# bontor_mbed_lowpan_rev_d.net
KiCad netlist of a schematic drawn in EAGLE
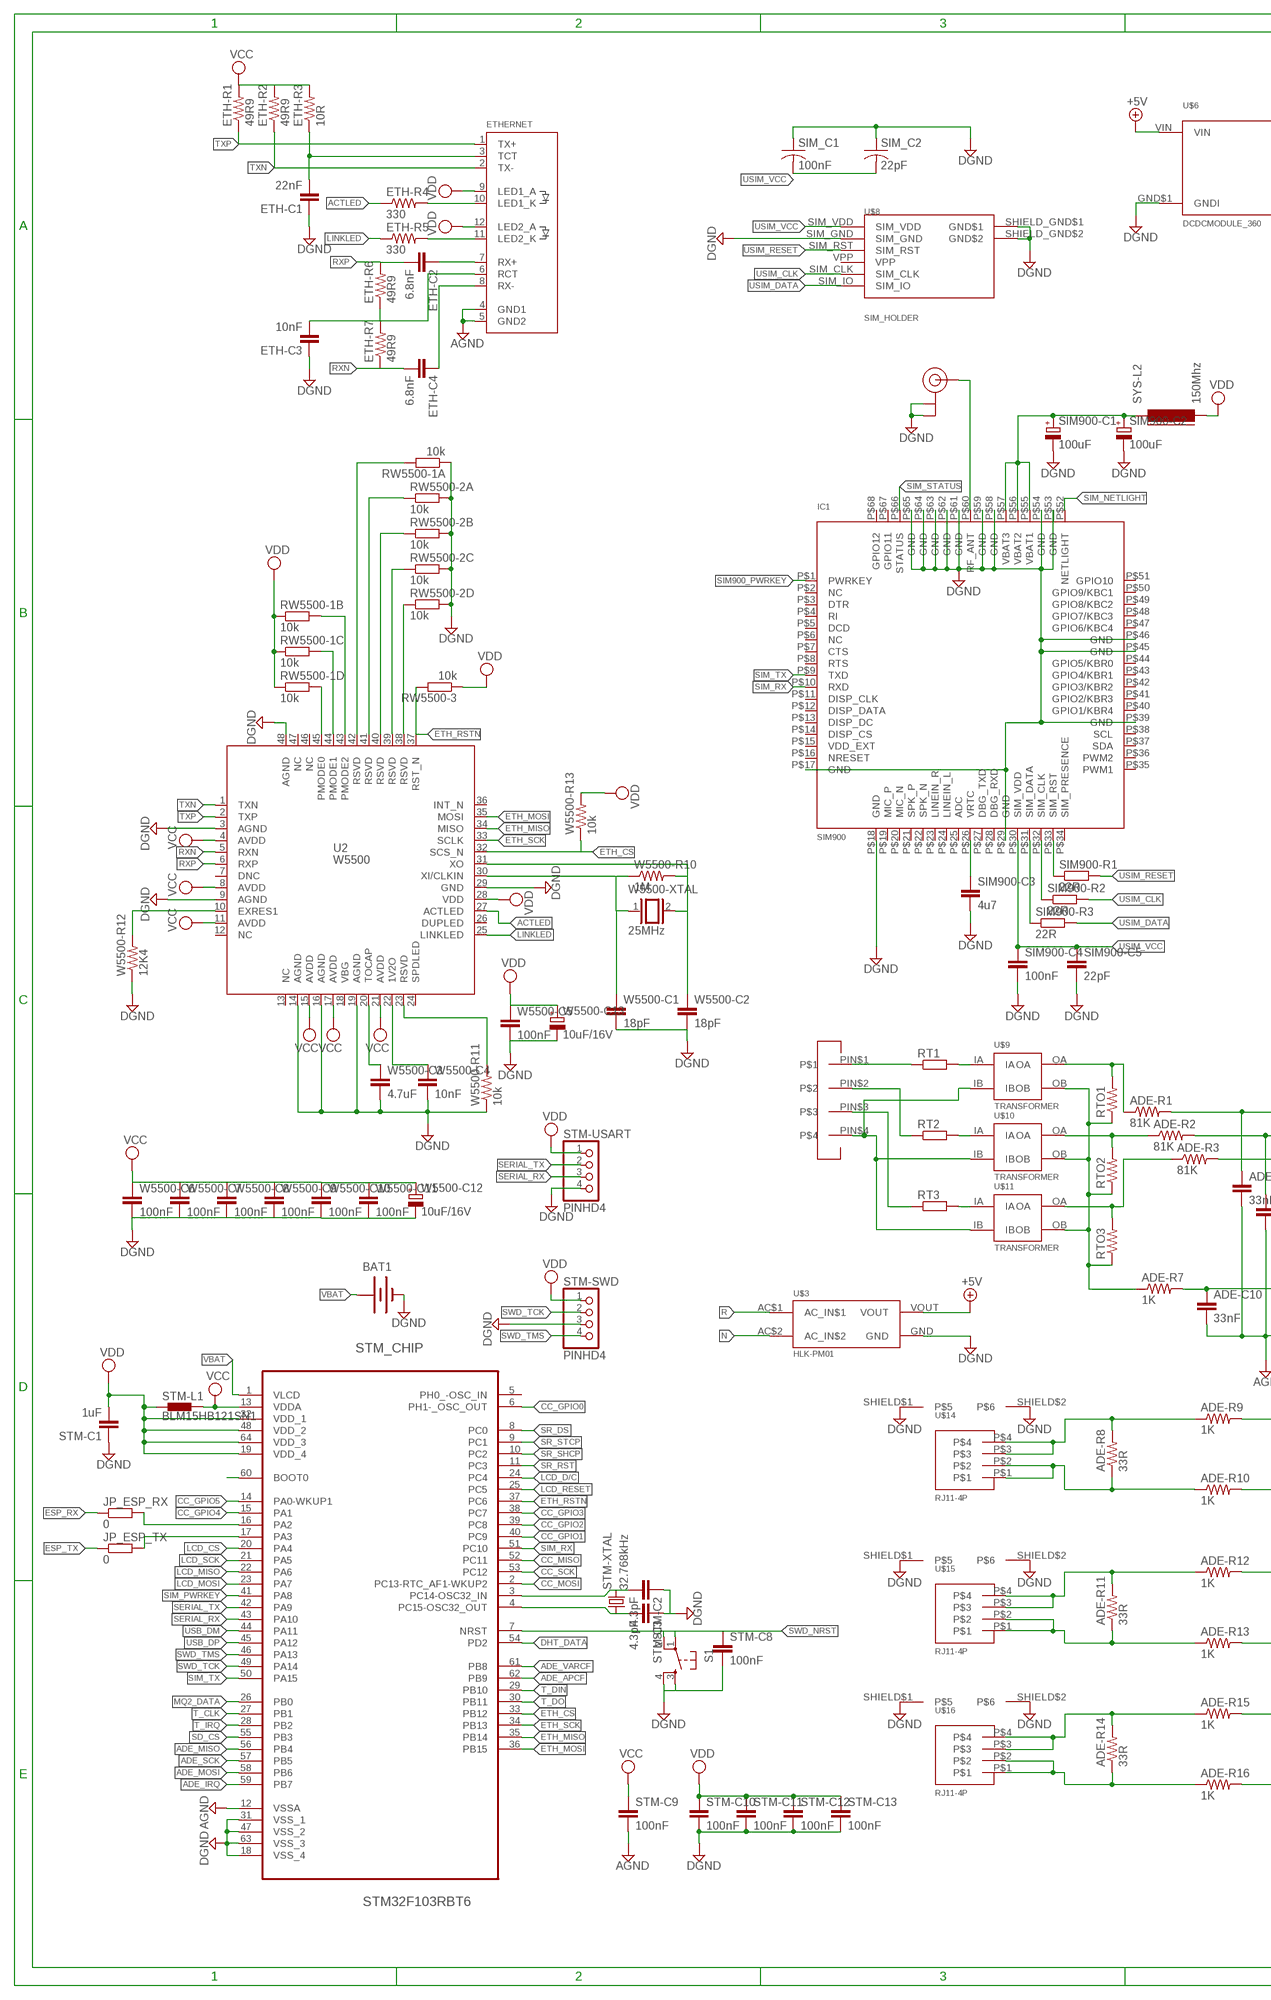
[diagram p0: schematic, sheet 1, part 1 of 2]
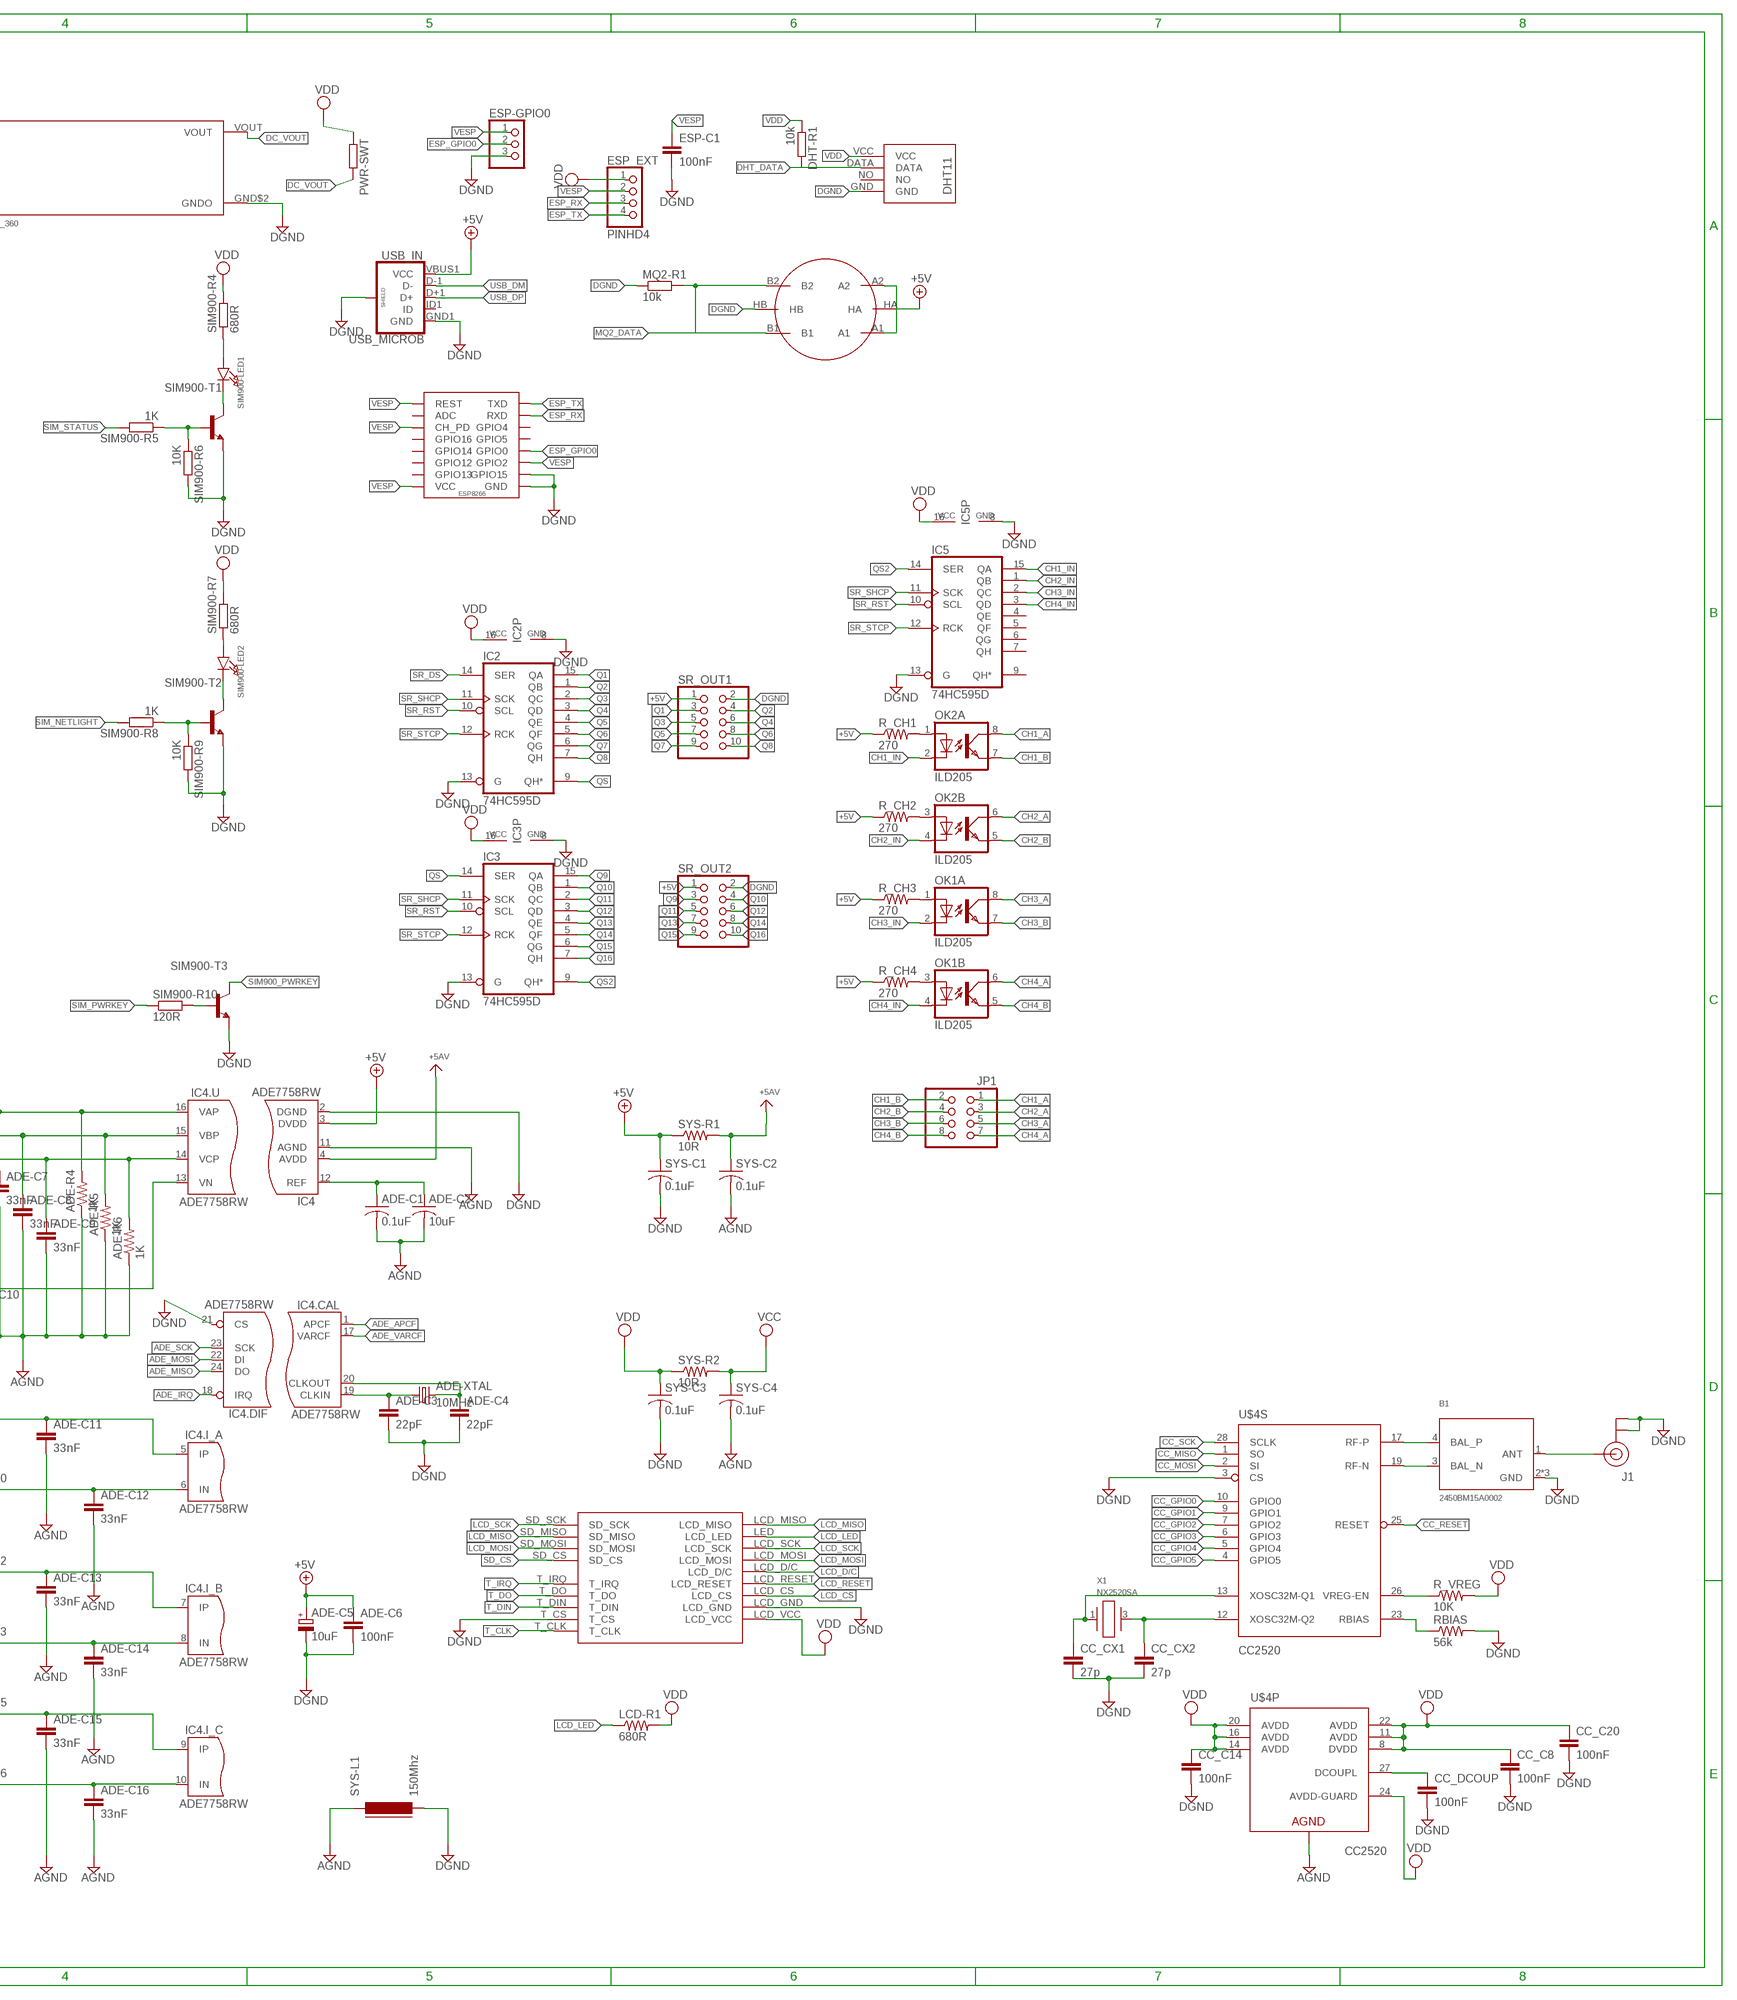
[diagram p1: schematic, sheet 1, part 2 of 2]

(export (version "E")
  (design (tool "Eeschema 10.0.6"))
  (components
    (comp (ref "ADE-C1")
      (value "0.1uF")
      (footprint "eagle-import:C0603@1")
      (libsource (lib "eagle-import") (part "C-USC0603"))
    )
    (comp (ref "ADE-C2")
      (value "10uF")
      (footprint "eagle-import:C0805K")
      (libsource (lib "eagle-import") (part "C-USC0805K"))
    )
    (comp (ref "ADE-C3")
      (value "22pF")
      (footprint "eagle-import:C0603")
      (libsource (lib "eagle-import") (part "C-EUC0603"))
    )
    (comp (ref "ADE-C4")
      (value "22pF")
      (footprint "eagle-import:C0603")
      (libsource (lib "eagle-import") (part "C-EUC0603"))
    )
    (comp (ref "ADE-C5")
      (value "10uF")
      (footprint "eagle-import:153CLV-0605")
      (libsource (lib "eagle-import") (part "CPOL-EU153CLV-0605"))
    )
    (comp (ref "ADE-C6")
      (value "100nF")
      (footprint "eagle-import:C0603")
      (libsource (lib "eagle-import") (part "C-EUC0603"))
    )
    (comp (ref "ADE-C7")
      (value "33nF")
      (footprint "eagle-import:0603-CAP")
      (libsource (lib "eagle-import") (part "CAP0603-CAP"))
    )
    (comp (ref "ADE-C8")
      (value "33nF")
      (footprint "eagle-import:0603-CAP")
      (libsource (lib "eagle-import") (part "CAP0603-CAP"))
    )
    (comp (ref "ADE-C9")
      (value "33nF")
      (footprint "eagle-import:0603-CAP")
      (libsource (lib "eagle-import") (part "CAP0603-CAP"))
    )
    (comp (ref "ADE-C10")
      (value "33nF")
      (footprint "eagle-import:0603-CAP")
      (libsource (lib "eagle-import") (part "CAP0603-CAP"))
    )
    (comp (ref "ADE-C11")
      (value "33nF")
      (footprint "eagle-import:0402-CAP")
      (libsource (lib "eagle-import") (part "CAP0402-CAP"))
    )
    (comp (ref "ADE-C12")
      (value "33nF")
      (footprint "eagle-import:0402-CAP")
      (libsource (lib "eagle-import") (part "CAP0402-CAP"))
    )
    (comp (ref "ADE-C13")
      (value "33nF")
      (footprint "eagle-import:0402-CAP")
      (libsource (lib "eagle-import") (part "CAP0402-CAP"))
    )
    (comp (ref "ADE-C14")
      (value "33nF")
      (footprint "eagle-import:0402-CAP")
      (libsource (lib "eagle-import") (part "CAP0402-CAP"))
    )
    (comp (ref "ADE-C15")
      (value "33nF")
      (footprint "eagle-import:0402-CAP")
      (libsource (lib "eagle-import") (part "CAP0402-CAP"))
    )
    (comp (ref "ADE-C16")
      (value "33nF")
      (footprint "eagle-import:0402-CAP")
      (libsource (lib "eagle-import") (part "CAP0402-CAP"))
    )
    (comp (ref "ADE-R1")
      (value "81K")
      (footprint "eagle-import:0603-RES")
      (libsource (lib "eagle-import") (part "RESISTOR0603-RES"))
    )
    (comp (ref "ADE-R2")
      (value "81K")
      (footprint "eagle-import:0603-RES")
      (libsource (lib "eagle-import") (part "RESISTOR0603-RES"))
    )
    (comp (ref "ADE-R3")
      (value "81K")
      (footprint "eagle-import:0603-RES")
      (libsource (lib "eagle-import") (part "RESISTOR0603-RES"))
    )
    (comp (ref "ADE-R4")
      (value "1K")
      (footprint "eagle-import:0603-RES")
      (libsource (lib "eagle-import") (part "RESISTOR0603-RES"))
    )
    (comp (ref "ADE-R5")
      (value "1K")
      (footprint "eagle-import:0603-RES")
      (libsource (lib "eagle-import") (part "RESISTOR0603-RES"))
    )
    (comp (ref "ADE-R6")
      (value "1K")
      (footprint "eagle-import:0603-RES")
      (libsource (lib "eagle-import") (part "RESISTOR0603-RES"))
    )
    (comp (ref "ADE-R7")
      (value "1K")
      (footprint "eagle-import:0603-RES")
      (libsource (lib "eagle-import") (part "RESISTOR0603-RES"))
    )
    (comp (ref "ADE-R8")
      (value "33R")
      (footprint "eagle-import:0402-RES")
      (libsource (lib "eagle-import") (part "RESISTOR0402-RES"))
    )
    (comp (ref "ADE-R9")
      (value "1K")
      (footprint "eagle-import:0402-RES")
      (libsource (lib "eagle-import") (part "RESISTOR0402-RES"))
    )
    (comp (ref "ADE-R10")
      (value "1K")
      (footprint "eagle-import:0402-RES")
      (libsource (lib "eagle-import") (part "RESISTOR0402-RES"))
    )
    (comp (ref "ADE-R11")
      (value "33R")
      (footprint "eagle-import:0402-RES")
      (libsource (lib "eagle-import") (part "RESISTOR0402-RES"))
    )
    (comp (ref "ADE-R12")
      (value "1K")
      (footprint "eagle-import:0402-RES")
      (libsource (lib "eagle-import") (part "RESISTOR0402-RES"))
    )
    (comp (ref "ADE-R13")
      (value "1K")
      (footprint "eagle-import:0402-RES")
      (libsource (lib "eagle-import") (part "RESISTOR0402-RES"))
    )
    (comp (ref "ADE-R14")
      (value "33R")
      (footprint "eagle-import:0402-RES")
      (libsource (lib "eagle-import") (part "RESISTOR0402-RES"))
    )
    (comp (ref "ADE-R15")
      (value "1K")
      (footprint "eagle-import:0402-RES")
      (libsource (lib "eagle-import") (part "RESISTOR0402-RES"))
    )
    (comp (ref "ADE-R16")
      (value "1K")
      (footprint "eagle-import:0402-RES")
      (libsource (lib "eagle-import") (part "RESISTOR0402-RES"))
    )
    (comp (ref "ADE-XTAL")
      (value "10MHz")
      (footprint "eagle-import:HC49US")
      (libsource (lib "eagle-import") (part "CRYSTALHC49US"))
    )
    (comp (ref "B1")
      (value "2450BM15A0002")
      (footprint "eagle-import:2450BM")
      (libsource (lib "eagle-import") (part "2450BM15A0002"))
    )
    (comp (ref "BAT1")
      (value "BATTERY12MM")
      (footprint "eagle-import:BATTCON_12MM")
      (libsource (lib "eagle-import") (part "BATTERY12MM"))
    )
    (comp (ref "CC_C8")
      (value "100nF")
      (footprint "eagle-import:C0402")
      (libsource (lib "eagle-import") (part "C-EUC0402"))
    )
    (comp (ref "CC_C14")
      (value "100nF")
      (footprint "eagle-import:C0402")
      (libsource (lib "eagle-import") (part "C-EUC0402"))
    )
    (comp (ref "CC_C20")
      (value "100nF")
      (footprint "eagle-import:C0402")
      (libsource (lib "eagle-import") (part "C-EUC0402"))
    )
    (comp (ref "CC_CX1")
      (value "27p")
      (footprint "eagle-import:C0201")
      (libsource (lib "eagle-import") (part "C-EUC0201"))
    )
    (comp (ref "CC_CX2")
      (value "27p")
      (footprint "eagle-import:C0201")
      (libsource (lib "eagle-import") (part "C-EUC0201"))
    )
    (comp (ref "CC_DCOUP")
      (value "100nF")
      (footprint "eagle-import:C0402")
      (libsource (lib "eagle-import") (part "C-EUC0402"))
    )
    (comp (ref "DHT-R1")
      (value "10k")
      (footprint "eagle-import:R0603")
      (libsource (lib "eagle-import") (part "resistor_R-EU_R0603"))
    )
    (comp (ref "ESP-C1")
      (value "100nF")
      (footprint "eagle-import:C0603")
      (libsource (lib "eagle-import") (part "C-EUC0603"))
    )
    (comp (ref "ESP-GPIO0")
      (value "PINHD-1X3")
      (footprint "eagle-import:1X03")
      (libsource (lib "eagle-import") (part "PINHD-1X3"))
    )
    (comp (ref "ESP_EXT")
      (value "PINHD4")
      (footprint "eagle-import:PINHD4")
      (libsource (lib "eagle-import") (part "PINHD4"))
    )
    (comp (ref "ETH-C1")
      (value "22nF")
      (footprint "eagle-import:C0603")
      (libsource (lib "eagle-import") (part "C-EUC0603"))
    )
    (comp (ref "ETH-C2")
      (value "6.8nF")
      (footprint "eagle-import:C0603")
      (libsource (lib "eagle-import") (part "C-EUC0603"))
    )
    (comp (ref "ETH-C3")
      (value "10nF")
      (footprint "eagle-import:C0603")
      (libsource (lib "eagle-import") (part "C-EUC0603"))
    )
    (comp (ref "ETH-C4")
      (value "6.8nF")
      (footprint "eagle-import:C0603")
      (libsource (lib "eagle-import") (part "C-EUC0603"))
    )
    (comp (ref "ETH-R1")
      (value "49R9")
      (footprint "eagle-import:R0603")
      (libsource (lib "eagle-import") (part "resistor_R-US_R0603"))
    )
    (comp (ref "ETH-R2")
      (value "49R9")
      (footprint "eagle-import:R0603")
      (libsource (lib "eagle-import") (part "resistor_R-US_R0603"))
    )
    (comp (ref "ETH-R3")
      (value "10R")
      (footprint "eagle-import:R0603")
      (libsource (lib "eagle-import") (part "resistor_R-US_R0603"))
    )
    (comp (ref "ETH-R4")
      (value "330")
      (footprint "eagle-import:R0603")
      (libsource (lib "eagle-import") (part "resistor_R-US_R0603"))
    )
    (comp (ref "ETH-R5")
      (value "330")
      (footprint "eagle-import:R0603")
      (libsource (lib "eagle-import") (part "resistor_R-US_R0603"))
    )
    (comp (ref "ETH-R6")
      (value "49R9")
      (footprint "eagle-import:R0603")
      (libsource (lib "eagle-import") (part "resistor_R-US_R0603"))
    )
    (comp (ref "ETH-R7")
      (value "49R9")
      (footprint "eagle-import:R0603")
      (libsource (lib "eagle-import") (part "resistor_R-US_R0603"))
    )
    (comp (ref "ETHERNET")
      (value "RJ45J0026D21BNL")
      (footprint "eagle-import:RJ45_PULSEJACK")
      (libsource (lib "eagle-import") (part "RJ45J0026D21BNL"))
    )
    (comp (ref "IC1")
      (value "SIM900")
      (footprint "eagle-import:SIM900_SMT")
      (libsource (lib "eagle-import") (part "GSM_SIM900_LITERAL"))
    )
    (comp (ref "IC2")
      (value "74HC595D")
      (footprint "eagle-import:SO16")
      (libsource (lib "eagle-import") (part "74595DHC"))
    )
    (comp (ref "IC3")
      (value "74HC595D")
      (footprint "eagle-import:SO16")
      (libsource (lib "eagle-import") (part "74595DHC"))
    )
    (comp (ref "IC4")
      (value "ADE7758RW")
      (footprint "eagle-import:SOIC24")
      (libsource (lib "eagle-import") (part "ADE7758RW"))
    )
    (comp (ref "IC5")
      (value "74HC595D")
      (footprint "eagle-import:SO16")
      (libsource (lib "eagle-import") (part "74595DHC"))
    )
    (comp (ref "J1")
      (value "U.FL")
      (footprint "eagle-import:U.FL")
      (libsource (lib "eagle-import") (part "SparkFun-Connectors_U.FL"))
    )
    (comp (ref "JP1")
      (value "PINHD-2X4")
      (footprint "eagle-import:2X04")
      (libsource (lib "eagle-import") (part "PINHD-2X4"))
    )
    (comp (ref "JP_ESP_RX")
      (value "0")
      (footprint "eagle-import:R0201")
      (libsource (lib "eagle-import") (part "R-EU_R0201"))
    )
    (comp (ref "JP_ESP_TX")
      (value "0")
      (footprint "eagle-import:R0201")
      (libsource (lib "eagle-import") (part "R-EU_R0201"))
    )
    (comp (ref "LCD-R1")
      (value "680R")
      (footprint "eagle-import:0603-RES")
      (libsource (lib "eagle-import") (part "RESISTOR0603-RES"))
    )
    (comp (ref "MQ2-R1")
      (value "10k")
      (footprint "eagle-import:R0603")
      (libsource (lib "eagle-import") (part "resistor_R-EU_R0603"))
    )
    (comp (ref "OK1")
      (value "ILD205")
      (footprint "eagle-import:SOIC08")
      (fields (field (name "MF") "VISHAY/TELEFUNKEN") (field (name "MPN") "ILD205T"))
      (libsource (lib "eagle-import") (part "ILD205"))
    )
    (comp (ref "OK2")
      (value "ILD205")
      (footprint "eagle-import:SOIC08")
      (fields (field (name "MF") "VISHAY/TELEFUNKEN") (field (name "MPN") "ILD205T"))
      (libsource (lib "eagle-import") (part "ILD205"))
    )
    (comp (ref "PWR-SWT")
      (value "R-EU_R0402")
      (footprint "eagle-import:R0402")
      (libsource (lib "eagle-import") (part "R-EU_R0402"))
    )
    (comp (ref "RBIAS")
      (value "56k")
      (footprint "eagle-import:0402-RES")
      (libsource (lib "eagle-import") (part "RESISTOR0402-RES"))
    )
    (comp (ref "RT1")
      (value "R-EU_0309/V")
      (footprint "eagle-import:0309V")
      (libsource (lib "eagle-import") (part "R-EU_0309/V"))
    )
    (comp (ref "RT2")
      (value "R-EU_0309/V")
      (footprint "eagle-import:0309V")
      (libsource (lib "eagle-import") (part "R-EU_0309/V"))
    )
    (comp (ref "RT3")
      (value "R-EU_0309/V")
      (footprint "eagle-import:0309V")
      (libsource (lib "eagle-import") (part "R-EU_0309/V"))
    )
    (comp (ref "RTO1")
      (value "R-US_0309_12")
      (footprint "eagle-import:0309_12")
      (libsource (lib "eagle-import") (part "R-US_0309_12"))
    )
    (comp (ref "RTO2")
      (value "R-US_0309_12")
      (footprint "eagle-import:0309_12")
      (libsource (lib "eagle-import") (part "R-US_0309_12"))
    )
    (comp (ref "RTO3")
      (value "R-US_0309_12")
      (footprint "eagle-import:0309_12")
      (libsource (lib "eagle-import") (part "R-US_0309_12"))
    )
    (comp (ref "RW5500-1")
      (value "10k")
      (footprint "eagle-import:RN8P-4R-CRA06S")
      (libsource (lib "eagle-import") (part "RESISTOR_ARRAY_4"))
    )
    (comp (ref "RW5500-2")
      (value "10k")
      (footprint "eagle-import:RN8P-4R-CRA06S")
      (libsource (lib "eagle-import") (part "RESISTOR_ARRAY_4"))
    )
    (comp (ref "RW5500-3")
      (value "10k")
      (footprint "eagle-import:R0603")
      (libsource (lib "eagle-import") (part "R-EU_R0603"))
    )
    (comp (ref "R_CH1")
      (value "270")
      (footprint "eagle-import:0603-RES")
      (libsource (lib "eagle-import") (part "RESISTOR0603-RES"))
    )
    (comp (ref "R_CH2")
      (value "270")
      (footprint "eagle-import:0603-RES")
      (libsource (lib "eagle-import") (part "RESISTOR0603-RES"))
    )
    (comp (ref "R_CH3")
      (value "270")
      (footprint "eagle-import:0603-RES")
      (libsource (lib "eagle-import") (part "RESISTOR0603-RES"))
    )
    (comp (ref "R_CH4")
      (value "270")
      (footprint "eagle-import:0603-RES")
      (libsource (lib "eagle-import") (part "RESISTOR0603-RES"))
    )
    (comp (ref "R_VREG")
      (value "10K")
      (footprint "eagle-import:0402-RES")
      (libsource (lib "eagle-import") (part "RESISTOR0402-RES"))
    )
    (comp (ref "S1")
      (value "TAC_SWITCHSMD")
      (footprint "eagle-import:TACTILE-SWITCH-SMD")
      (libsource (lib "eagle-import") (part "TAC_SWITCHSMD"))
    )
    (comp (ref "SENSOR-MQ2")
      (value "METHANE_SENSOR")
      (footprint "eagle-import:MQ-3")
      (libsource (lib "eagle-import") (part "METHANE_SENSOR"))
    )
    (comp (ref "SIM900-C1")
      (value "100uF")
      (footprint "eagle-import:153CLV-0605")
      (libsource (lib "eagle-import") (part "CPOL-EU153CLV-0605"))
    )
    (comp (ref "SIM900-C2")
      (value "100uF")
      (footprint "eagle-import:153CLV-0605")
      (libsource (lib "eagle-import") (part "CPOL-EU153CLV-0605"))
    )
    (comp (ref "SIM900-C3")
      (value "4u7")
      (footprint "eagle-import:C0603")
      (libsource (lib "eagle-import") (part "C-EUC0603"))
    )
    (comp (ref "SIM900-C4")
      (value "100nF")
      (footprint "eagle-import:C0603")
      (libsource (lib "eagle-import") (part "C-EUC0603"))
    )
    (comp (ref "SIM900-C5")
      (value "22pF")
      (footprint "eagle-import:C0603")
      (libsource (lib "eagle-import") (part "C-EUC0603"))
    )
    (comp (ref "SIM900-LED1")
      (value "LED0805_NOOUTLINE")
      (footprint "eagle-import:CHIPLED_0805_NOOUTLINE")
      (libsource (lib "eagle-import") (part "LED0805_NOOUTLINE"))
    )
    (comp (ref "SIM900-LED2")
      (value "LED0805_NOOUTLINE")
      (footprint "eagle-import:CHIPLED_0805_NOOUTLINE")
      (libsource (lib "eagle-import") (part "LED0805_NOOUTLINE"))
    )
    (comp (ref "SIM900-R1")
      (value "22R")
      (footprint "eagle-import:R0603")
      (libsource (lib "eagle-import") (part "R-EU_R0603"))
    )
    (comp (ref "SIM900-R2")
      (value "22R")
      (footprint "eagle-import:R0603")
      (libsource (lib "eagle-import") (part "R-EU_R0603"))
    )
    (comp (ref "SIM900-R3")
      (value "22R")
      (footprint "eagle-import:R0603")
      (libsource (lib "eagle-import") (part "R-EU_R0603"))
    )
    (comp (ref "SIM900-R4")
      (value "680R")
      (footprint "eagle-import:R0402")
      (libsource (lib "eagle-import") (part "R-EU_R0402"))
    )
    (comp (ref "SIM900-R5")
      (value "1K")
      (footprint "eagle-import:R0603")
      (libsource (lib "eagle-import") (part "R-EU_R0603"))
    )
    (comp (ref "SIM900-R6")
      (value "10K")
      (footprint "eagle-import:R0603")
      (libsource (lib "eagle-import") (part "R-EU_R0603"))
    )
    (comp (ref "SIM900-R7")
      (value "680R")
      (footprint "eagle-import:R0603")
      (libsource (lib "eagle-import") (part "R-EU_R0603"))
    )
    (comp (ref "SIM900-R8")
      (value "1K")
      (footprint "eagle-import:R0603")
      (libsource (lib "eagle-import") (part "R-EU_R0603"))
    )
    (comp (ref "SIM900-R9")
      (value "10K")
      (footprint "eagle-import:R0603")
      (libsource (lib "eagle-import") (part "R-EU_R0603"))
    )
    (comp (ref "SIM900-R10")
      (value "120R")
      (footprint "eagle-import:R0603")
      (libsource (lib "eagle-import") (part "resistor_R-EU_R0603"))
    )
    (comp (ref "SIM900-T1")
      (value "MMBT2222ALT1-NPN-SOT23-BEC")
      (footprint "eagle-import:SOT23-BEC")
      (libsource (lib "eagle-import") (part "-NPN-SOT23-BECMMBT2222ALT1"))
    )
    (comp (ref "SIM900-T2")
      (value "MMBT2222ALT1-NPN-SOT23-BEC")
      (footprint "eagle-import:SOT23-BEC")
      (libsource (lib "eagle-import") (part "-NPN-SOT23-BECMMBT2222ALT1"))
    )
    (comp (ref "SIM900-T3")
      (value "MMBT2222ALT1-NPN-SOT23-BEC")
      (footprint "eagle-import:SOT23-BEC")
      (libsource (lib "eagle-import") (part "transistor-neu-to92_-NPN-SOT23-BECMMBT2222ALT1"))
    )
    (comp (ref "SIM_C1")
      (value "100nF")
      (footprint "eagle-import:C0603K")
      (libsource (lib "eagle-import") (part "C-USC0603K"))
    )
    (comp (ref "SIM_C2")
      (value "22pF")
      (footprint "eagle-import:C0603K")
      (libsource (lib "eagle-import") (part "C-USC0603K"))
    )
    (comp (ref "SR_OUT1")
      (value "PINHD-2X5")
      (footprint "eagle-import:2X05")
      (libsource (lib "eagle-import") (part "PINHD-2X5"))
    )
    (comp (ref "SR_OUT2")
      (value "PINHD-2X5")
      (footprint "eagle-import:2X05")
      (libsource (lib "eagle-import") (part "PINHD-2X5"))
    )
    (comp (ref "STM-C1")
      (value "1uF")
      (footprint "eagle-import:C0603")
      (libsource (lib "eagle-import") (part "C-EUC0603"))
    )
    (comp (ref "STM-C2")
      (value "4.3pF")
      (footprint "eagle-import:C0603")
      (libsource (lib "eagle-import") (part "C-EUC0603"))
    )
    (comp (ref "STM-C3")
      (value "4.3pF")
      (footprint "eagle-import:C0603")
      (libsource (lib "eagle-import") (part "C-EUC0603"))
    )
    (comp (ref "STM-C8")
      (value "100nF")
      (footprint "eagle-import:C0603")
      (libsource (lib "eagle-import") (part "C-EUC0603"))
    )
    (comp (ref "STM-C9")
      (value "100nF")
      (footprint "eagle-import:C0603")
      (libsource (lib "eagle-import") (part "C-EUC0603"))
    )
    (comp (ref "STM-C10")
      (value "100nF")
      (footprint "eagle-import:C0603")
      (libsource (lib "eagle-import") (part "C-EUC0603"))
    )
    (comp (ref "STM-C11")
      (value "100nF")
      (footprint "eagle-import:C0603")
      (libsource (lib "eagle-import") (part "C-EUC0603"))
    )
    (comp (ref "STM-C12")
      (value "100nF")
      (footprint "eagle-import:C0603")
      (libsource (lib "eagle-import") (part "C-EUC0603"))
    )
    (comp (ref "STM-C13")
      (value "100nF")
      (footprint "eagle-import:C0603")
      (libsource (lib "eagle-import") (part "C-EUC0603"))
    )
    (comp (ref "STM-L1")
      (value "BLM15HB121SN1")
      (footprint "eagle-import:0402")
      (libsource (lib "eagle-import") (part "BLM15HB121SN1"))
    )
    (comp (ref "STM-SWD")
      (value "PINHD4")
      (footprint "eagle-import:PINHD4")
      (libsource (lib "eagle-import") (part "PINHD4"))
    )
    (comp (ref "STM-USART")
      (value "PINHD4")
      (footprint "eagle-import:PINHD4")
      (libsource (lib "eagle-import") (part "PINHD4"))
    )
    (comp (ref "STM-XTAL")
      (value "32.768kHz")
      (footprint "eagle-import:TC26H")
      (libsource (lib "eagle-import") (part "CRYSTALTC26H"))
    )
    (comp (ref "STM_CHIP")
      (value "STM32F103RBT6")
      (footprint "eagle-import:QFP50P1200X1200X160-64N")
      (fields (field (name "MPN") "STM32L152RBT6"))
      (libsource (lib "eagle-import") (part "STM32L152RBT6"))
    )
    (comp (ref "SYS-C1")
      (value "0.1uF")
      (footprint "eagle-import:C0603@1")
      (libsource (lib "eagle-import") (part "C-USC0603"))
    )
    (comp (ref "SYS-C2")
      (value "0.1uF")
      (footprint "eagle-import:C0603@1")
      (libsource (lib "eagle-import") (part "C-USC0603"))
    )
    (comp (ref "SYS-C3")
      (value "0.1uF")
      (footprint "eagle-import:C0603@1")
      (libsource (lib "eagle-import") (part "C-USC0603"))
    )
    (comp (ref "SYS-C4")
      (value "0.1uF")
      (footprint "eagle-import:C0603@1")
      (libsource (lib "eagle-import") (part "C-USC0603"))
    )
    (comp (ref "SYS-L1")
      (value "150Mhz")
      (footprint "eagle-import:FB805")
      (libsource (lib "eagle-import") (part "FERRITE-0805"))
    )
    (comp (ref "SYS-L2")
      (value "150Mhz")
      (footprint "eagle-import:FB805")
      (libsource (lib "eagle-import") (part "FERRITE-0805"))
    )
    (comp (ref "SYS-R1")
      (value "10R")
      (footprint "eagle-import:0603-RES")
      (libsource (lib "eagle-import") (part "RESISTOR0603-RES"))
    )
    (comp (ref "SYS-R2")
      (value "10R")
      (footprint "eagle-import:0603-RES")
      (libsource (lib "eagle-import") (part "RESISTOR0603-RES"))
    )
    (comp (ref "U$3")
      (value "HLK-PM01")
      (footprint "eagle-import:HLK-PM01")
      (libsource (lib "eagle-import") (part "HLK-PM01"))
    )
    (comp (ref "U$4")
      (value "CC2520")
      (footprint "eagle-import:QFN50P500X500X100-29N")
      (libsource (lib "eagle-import") (part "CC2520"))
    )
    (comp (ref "U$5")
      (value "ESP8266WI12")
      (footprint "eagle-import:WI12")
      (libsource (lib "eagle-import") (part "ESP8266WI12"))
    )
    (comp (ref "U$6")
      (value "DCDCMODULE_360")
      (footprint "eagle-import:DCDCMODULE-360")
      (libsource (lib "eagle-import") (part "DCDCMODULE_360"))
    )
    (comp (ref "U$7")
      (value "U.FL")
      (footprint "eagle-import:U.FL")
      (libsource (lib "eagle-import") (part "U.FL"))
    )
    (comp (ref "U$8")
      (value "SIM_HOLDER")
      (footprint "eagle-import:SIMHOLDER-PUSHPUSH")
      (libsource (lib "eagle-import") (part "SIM_HOLDER"))
    )
    (comp (ref "U$9")
      (value "TRANSFORMER")
      (footprint "eagle-import:TV16")
      (libsource (lib "eagle-import") (part "TRANSFORMER"))
    )
    (comp (ref "U$10")
      (value "TRANSFORMER")
      (footprint "eagle-import:TV16")
      (libsource (lib "eagle-import") (part "TRANSFORMER"))
    )
    (comp (ref "U$11")
      (value "TRANSFORMER")
      (footprint "eagle-import:TV16")
      (libsource (lib "eagle-import") (part "TRANSFORMER"))
    )
    (comp (ref "U$12")
      (value "TERMINAL_BLOCK_TW")
      (footprint "eagle-import:TERMINAL-TWO-WAY")
      (libsource (lib "eagle-import") (part "TERMINAL_BLOCK_TW"))
    )
    (comp (ref "U$13")
      (value "LCD_2.4")
      (footprint "eagle-import:LCD_TOUCH_2-4")
      (libsource (lib "eagle-import") (part "LCD_2.4"))
    )
    (comp (ref "U$14")
      (value "RJ11-4P")
      (footprint "eagle-import:RJ11-4P")
      (libsource (lib "eagle-import") (part "RJ11-4P"))
    )
    (comp (ref "U$15")
      (value "RJ11-4P")
      (footprint "eagle-import:RJ11-4P")
      (libsource (lib "eagle-import") (part "RJ11-4P"))
    )
    (comp (ref "U$16")
      (value "RJ11-4P")
      (footprint "eagle-import:RJ11-4P")
      (libsource (lib "eagle-import") (part "RJ11-4P"))
    )
    (comp (ref "U$17")
      (value "DHT11")
      (footprint "eagle-import:DHT11")
      (libsource (lib "eagle-import") (part "DHT11"))
    )
    (comp (ref "U2")
      (value "W5500")
      (footprint "eagle-import:W5500")
      (libsource (lib "eagle-import") (part "W5500"))
    )
    (comp (ref "USB_IN")
      (value "USB_MICROB")
      (footprint "eagle-import:USB-B-MICRO-SMD_V03")
      (libsource (lib "eagle-import") (part "USB_MICROB_PLUGCONN-11752"))
    )
    (comp (ref "W5500-C1")
      (value "18pF")
      (footprint "eagle-import:C0603")
      (libsource (lib "eagle-import") (part "C-EUC0603"))
    )
    (comp (ref "W5500-C2")
      (value "18pF")
      (footprint "eagle-import:C0603")
      (libsource (lib "eagle-import") (part "C-EUC0603"))
    )
    (comp (ref "W5500-C3")
      (value "4.7uF")
      (footprint "eagle-import:C0603")
      (libsource (lib "eagle-import") (part "C-EUC0603"))
    )
    (comp (ref "W5500-C4")
      (value "10nF")
      (footprint "eagle-import:C0603")
      (libsource (lib "eagle-import") (part "C-EUC0603"))
    )
    (comp (ref "W5500-C5")
      (value "100nF")
      (footprint "eagle-import:C0603")
      (libsource (lib "eagle-import") (part "C-EUC0603"))
    )
    (comp (ref "W5500-C6")
      (value "100nF")
      (footprint "eagle-import:C0603")
      (libsource (lib "eagle-import") (part "C-EUC0603"))
    )
    (comp (ref "W5500-C7")
      (value "100nF")
      (footprint "eagle-import:C0603")
      (libsource (lib "eagle-import") (part "C-EUC0603"))
    )
    (comp (ref "W5500-C8")
      (value "100nF")
      (footprint "eagle-import:C0603")
      (libsource (lib "eagle-import") (part "C-EUC0603"))
    )
    (comp (ref "W5500-C9")
      (value "100nF")
      (footprint "eagle-import:C0603")
      (libsource (lib "eagle-import") (part "C-EUC0603"))
    )
    (comp (ref "W5500-C10")
      (value "100nF")
      (footprint "eagle-import:C0603")
      (libsource (lib "eagle-import") (part "C-EUC0603"))
    )
    (comp (ref "W5500-C11")
      (value "100nF")
      (footprint "eagle-import:C0603")
      (libsource (lib "eagle-import") (part "C-EUC0603"))
    )
    (comp (ref "W5500-C12")
      (value "10uF/16V")
      (footprint "eagle-import:153CLV-0605")
      (libsource (lib "eagle-import") (part "CPOL-EU153CLV-0605"))
    )
    (comp (ref "W5500-C13")
      (value "10uF/16V")
      (footprint "eagle-import:153CLV-0605")
      (libsource (lib "eagle-import") (part "CPOL-EU153CLV-0605"))
    )
    (comp (ref "W5500-R10")
      (value "1M")
      (footprint "eagle-import:R0603")
      (libsource (lib "eagle-import") (part "resistor_R-US_R0603"))
    )
    (comp (ref "W5500-R11")
      (value "10k")
      (footprint "eagle-import:R0603")
      (libsource (lib "eagle-import") (part "resistor_R-US_R0603"))
    )
    (comp (ref "W5500-R12")
      (value "12K4")
      (footprint "eagle-import:R0805")
      (libsource (lib "eagle-import") (part "resistor_R-US_R0805"))
    )
    (comp (ref "W5500-R13")
      (value "10k")
      (footprint "eagle-import:R0603")
      (libsource (lib "eagle-import") (part "resistor_R-US_R0603"))
    )
    (comp (ref "W5500-XTAL")
      (value "25MHz")
      (footprint "eagle-import:QS")
      (libsource (lib "eagle-import") (part "XTAL/S"))
    )
    (comp (ref "X1")
      (value "NX2520SA")
      (footprint "eagle-import:NX2520SA")
      (libsource (lib "eagle-import") (part "NX2520SA"))
    )
  )
  (nets
    (net (code "1") (name "+5AV") (class "Default")
      (node (ref "IC4") (pin "4") (pinfunction "AVDD_4") (pintype "power_in"))
      (node (ref "SYS-C2") (pin "1") (pinfunction "1_1") (pintype "passive"))
      (node (ref "SYS-R1") (pin "2") (pinfunction "2_2") (pintype "passive"))
    )
    (net (code "2") (name "+5V") (class "Default")
      (node (ref "ADE-C5") (pin "+") (pinfunction "+_+") (pintype "passive"))
      (node (ref "ADE-C6") (pin "1") (pinfunction "1_1") (pintype "passive"))
      (node (ref "IC4") (pin "3") (pinfunction "DVDD_3") (pintype "power_in"))
      (node (ref "R_CH1") (pin "1") (pinfunction "1_1") (pintype "passive"))
      (node (ref "R_CH2") (pin "1") (pinfunction "1_1") (pintype "passive"))
      (node (ref "R_CH3") (pin "1") (pinfunction "1_1") (pintype "passive"))
      (node (ref "R_CH4") (pin "1") (pinfunction "1_1") (pintype "passive"))
      (node (ref "SENSOR-MQ2") (pin "A1") (pinfunction "A1_A1") (pintype "bidirectional"))
      (node (ref "SENSOR-MQ2") (pin "A2") (pinfunction "A2_A2") (pintype "bidirectional"))
      (node (ref "SENSOR-MQ2") (pin "HA") (pinfunction "HA_HA") (pintype "bidirectional"))
      (node (ref "SR_OUT1") (pin "1") (pinfunction "1_1") (pintype "passive"))
      (node (ref "SR_OUT2") (pin "1") (pinfunction "1_1") (pintype "passive"))
      (node (ref "SYS-C1") (pin "1") (pinfunction "1_1") (pintype "passive"))
      (node (ref "SYS-R1") (pin "1") (pinfunction "1_1") (pintype "passive"))
      (node (ref "U$3") (pin "VOUT") (pinfunction "VOUT_VOUT") (pintype "bidirectional"))
      (node (ref "U$6") (pin "VIN") (pinfunction "VIN_VIN") (pintype "bidirectional"))
      (node (ref "USB_IN") (pin "VBUS1") (pinfunction "VCC_VBUS1") (pintype "bidirectional"))
    )
    (net (code "3") (name "/GPIO11") (class "Default")
      (node (ref "IC1") (pin "P$67") (pinfunction "GPIO11_P$67") (pintype "power_in"))
    )
    (net (code "4") (name "/GPIO12") (class "Default")
      (node (ref "IC1") (pin "P$68") (pinfunction "GPIO12_P$68") (pintype "power_in"))
    )
    (net (code "5") (name "ACTLED") (class "Default")
      (node (ref "ETH-R4") (pin "1") (pinfunction "1_1") (pintype "passive"))
      (node (ref "U2") (pin "27") (pinfunction "ACTLED_27") (pintype "passive"))
    )
    (net (code "6") (name "ADE_APCF") (class "Default")
      (node (ref "IC4") (pin "1") (pinfunction "APCF_1") (pintype "output"))
      (node (ref "STM_CHIP") (pin "62") (pinfunction "PB9_62") (pintype "bidirectional"))
    )
    (net (code "7") (name "ADE_IRQ") (class "Default")
      (node (ref "IC4") (pin "18") (pinfunction "IRQ_18") (pintype "output"))
      (node (ref "STM_CHIP") (pin "59") (pinfunction "PB7_59") (pintype "bidirectional"))
    )
    (net (code "8") (name "ADE_MISO") (class "Default")
      (node (ref "IC4") (pin "24") (pinfunction "DO_24") (pintype "output"))
      (node (ref "STM_CHIP") (pin "56") (pinfunction "PB4_56") (pintype "bidirectional"))
    )
    (net (code "9") (name "ADE_MOSI") (class "Default")
      (node (ref "IC4") (pin "22") (pinfunction "DI_22") (pintype "input"))
      (node (ref "STM_CHIP") (pin "58") (pinfunction "PB6_58") (pintype "bidirectional"))
    )
    (net (code "10") (name "ADE_SCK") (class "Default")
      (node (ref "IC4") (pin "23") (pinfunction "SCK_23") (pintype "input"))
      (node (ref "STM_CHIP") (pin "57") (pinfunction "PB5_57") (pintype "bidirectional"))
    )
    (net (code "11") (name "ADE_VARCF") (class "Default")
      (node (ref "IC4") (pin "17") (pinfunction "VARCF_17") (pintype "output"))
      (node (ref "STM_CHIP") (pin "61") (pinfunction "PB8_61") (pintype "bidirectional"))
    )
    (net (code "12") (name "AGND") (class "Default")
      (node (ref "ADE-C1") (pin "2") (pinfunction "2_2") (pintype "passive"))
      (node (ref "ADE-C10") (pin "2") (pinfunction "2_2") (pintype "passive"))
      (node (ref "ADE-C11") (pin "2") (pinfunction "2_2") (pintype "passive"))
      (node (ref "ADE-C12") (pin "2") (pinfunction "2_2") (pintype "passive"))
      (node (ref "ADE-C13") (pin "2") (pinfunction "2_2") (pintype "passive"))
      (node (ref "ADE-C14") (pin "2") (pinfunction "2_2") (pintype "passive"))
      (node (ref "ADE-C15") (pin "2") (pinfunction "2_2") (pintype "passive"))
      (node (ref "ADE-C16") (pin "2") (pinfunction "2_2") (pintype "passive"))
      (node (ref "ADE-C2") (pin "2") (pinfunction "2_2") (pintype "passive"))
      (node (ref "ADE-C7") (pin "2") (pinfunction "2_2") (pintype "passive"))
      (node (ref "ADE-C8") (pin "2") (pinfunction "2_2") (pintype "passive"))
      (node (ref "ADE-C9") (pin "2") (pinfunction "2_2") (pintype "passive"))
      (node (ref "ADE-R4") (pin "1") (pinfunction "1_1") (pintype "passive"))
      (node (ref "ADE-R5") (pin "1") (pinfunction "1_1") (pintype "passive"))
      (node (ref "ADE-R6") (pin "1") (pinfunction "1_1") (pintype "passive"))
      (node (ref "ETHERNET") (pin "4") (pinfunction "GND1_4") (pintype "bidirectional"))
      (node (ref "ETHERNET") (pin "5") (pinfunction "GND2_5") (pintype "bidirectional"))
      (node (ref "IC4") (pin "11") (pinfunction "AGND_11") (pintype "power_in"))
      (node (ref "STM-C9") (pin "2") (pinfunction "2_2") (pintype "passive"))
      (node (ref "STM_CHIP") (pin "12") (pinfunction "VSSA_12") (pintype "power_in"))
      (node (ref "SYS-C2") (pin "2") (pinfunction "2_2") (pintype "passive"))
      (node (ref "SYS-C4") (pin "2") (pinfunction "2_2") (pintype "passive"))
      (node (ref "SYS-L1") (pin "1") (pinfunction "1_1") (pintype "passive"))
      (node (ref "U$4") (pin "29") (pinfunction "AGND_29") (pintype "power_in"))
    )
    (net (code "13") (name "CC_GPIO0") (class "Default")
      (node (ref "STM_CHIP") (pin "6") (pinfunction "PH1-_OSC_OUT_6") (pintype "bidirectional"))
      (node (ref "U$4") (pin "10") (pinfunction "GPIO0_10") (pintype "output"))
    )
    (net (code "14") (name "CC_GPIO1") (class "Default")
      (node (ref "STM_CHIP") (pin "40") (pinfunction "PC9_40") (pintype "bidirectional"))
      (node (ref "U$4") (pin "9") (pinfunction "GPIO1_9") (pintype "output"))
    )
    (net (code "15") (name "CC_GPIO2") (class "Default")
      (node (ref "STM_CHIP") (pin "39") (pinfunction "PC8_39") (pintype "bidirectional"))
      (node (ref "U$4") (pin "7") (pinfunction "GPIO2_7") (pintype "bidirectional"))
    )
    (net (code "16") (name "CC_GPIO3") (class "Default")
      (node (ref "STM_CHIP") (pin "38") (pinfunction "PC7_38") (pintype "bidirectional"))
      (node (ref "U$4") (pin "6") (pinfunction "GPIO3_6") (pintype "bidirectional"))
    )
    (net (code "17") (name "CC_GPIO4") (class "Default")
      (node (ref "STM_CHIP") (pin "15") (pinfunction "PA1_15") (pintype "bidirectional"))
      (node (ref "U$4") (pin "5") (pinfunction "GPIO4_5") (pintype "bidirectional"))
    )
    (net (code "18") (name "CC_GPIO5") (class "Default")
      (node (ref "STM_CHIP") (pin "14") (pinfunction "PA0-WKUP1_14") (pintype "bidirectional"))
      (node (ref "U$4") (pin "4") (pinfunction "GPIO5_4") (pintype "bidirectional"))
    )
    (net (code "19") (name "CC_MISO") (class "Default")
      (node (ref "STM_CHIP") (pin "52") (pinfunction "PC11_52") (pintype "bidirectional"))
      (node (ref "U$4") (pin "1") (pinfunction "SO_1") (pintype "output"))
    )
    (net (code "20") (name "CC_MOSI") (class "Default")
      (node (ref "STM_CHIP") (pin "2") (pinfunction "PC13-RTC_AF1-WKUP2_2") (pintype "bidirectional"))
      (node (ref "U$4") (pin "2") (pinfunction "SI_2") (pintype "input"))
    )
    (net (code "21") (name "CC_RESET") (class "Default")
      (node (ref "U$4") (pin "25") (pinfunction "RESET_25") (pintype "input"))
    )
    (net (code "22") (name "CC_SCK") (class "Default")
      (node (ref "STM_CHIP") (pin "53") (pinfunction "PC12_53") (pintype "bidirectional"))
      (node (ref "U$4") (pin "28") (pinfunction "SCLK_28") (pintype "input"))
    )
    (net (code "23") (name "CH1_A") (class "Default")
      (node (ref "JP1") (pin "1") (pinfunction "1_1") (pintype "passive"))
      (node (ref "OK2") (pin "8") (pinfunction "COL_8") (pintype "passive"))
    )
    (net (code "24") (name "CH1_B") (class "Default")
      (node (ref "JP1") (pin "2") (pinfunction "2_2") (pintype "passive"))
      (node (ref "OK2") (pin "7") (pinfunction "EMIT_7") (pintype "passive"))
    )
    (net (code "25") (name "CH1_IN") (class "Default")
      (node (ref "IC5") (pin "15") (pinfunction "QA_15") (pintype "tri_state"))
      (node (ref "OK2") (pin "2") (pinfunction "C_2") (pintype "passive"))
    )
    (net (code "26") (name "CH2_A") (class "Default")
      (node (ref "JP1") (pin "3") (pinfunction "3_3") (pintype "passive"))
      (node (ref "OK2") (pin "6") (pinfunction "COL_6") (pintype "passive"))
    )
    (net (code "27") (name "CH2_B") (class "Default")
      (node (ref "JP1") (pin "4") (pinfunction "4_4") (pintype "passive"))
      (node (ref "OK2") (pin "5") (pinfunction "EMIT_5") (pintype "passive"))
    )
    (net (code "28") (name "CH2_IN") (class "Default")
      (node (ref "IC5") (pin "1") (pinfunction "QB_1") (pintype "tri_state"))
      (node (ref "OK2") (pin "4") (pinfunction "C_4") (pintype "passive"))
    )
    (net (code "29") (name "CH3_A") (class "Default")
      (node (ref "JP1") (pin "5") (pinfunction "5_5") (pintype "passive"))
      (node (ref "OK1") (pin "8") (pinfunction "COL_8") (pintype "passive"))
    )
    (net (code "30") (name "CH3_B") (class "Default")
      (node (ref "JP1") (pin "6") (pinfunction "6_6") (pintype "passive"))
      (node (ref "OK1") (pin "7") (pinfunction "EMIT_7") (pintype "passive"))
    )
    (net (code "31") (name "CH3_IN") (class "Default")
      (node (ref "IC5") (pin "2") (pinfunction "QC_2") (pintype "tri_state"))
      (node (ref "OK1") (pin "2") (pinfunction "C_2") (pintype "passive"))
    )
    (net (code "32") (name "CH4_A") (class "Default")
      (node (ref "JP1") (pin "7") (pinfunction "7_7") (pintype "passive"))
      (node (ref "OK1") (pin "6") (pinfunction "COL_6") (pintype "passive"))
    )
    (net (code "33") (name "CH4_B") (class "Default")
      (node (ref "JP1") (pin "8") (pinfunction "8_8") (pintype "passive"))
      (node (ref "OK1") (pin "5") (pinfunction "EMIT_5") (pintype "passive"))
    )
    (net (code "34") (name "CH4_IN") (class "Default")
      (node (ref "IC5") (pin "3") (pinfunction "QD_3") (pintype "tri_state"))
      (node (ref "OK1") (pin "4") (pinfunction "C_4") (pintype "passive"))
    )
    (net (code "35") (name "DC_VOUT") (class "Default")
      (node (ref "PWR-SWT") (pin "2") (pinfunction "2_2") (pintype "passive"))
      (node (ref "U$6") (pin "VOUT") (pinfunction "VOUT_VOUT") (pintype "bidirectional"))
    )
    (net (code "36") (name "DGND") (class "Default")
      (node (ref "ADE-C3") (pin "2") (pinfunction "2_2") (pintype "passive"))
      (node (ref "ADE-C4") (pin "2") (pinfunction "2_2") (pintype "passive"))
      (node (ref "ADE-C5") (pin "-") (pinfunction "-_-") (pintype "passive"))
      (node (ref "ADE-C6") (pin "2") (pinfunction "2_2") (pintype "passive"))
      (node (ref "B1") (pin "2") (pinfunction "GND_2") (pintype "bidirectional"))
      (node (ref "B1") (pin "5") (pinfunction "GND_5") (pintype "bidirectional"))
      (node (ref "B1") (pin "6") (pinfunction "GND_6") (pintype "bidirectional"))
      (node (ref "BAT1") (pin "GND") (pinfunction "-_GND") (pintype "power_in"))
      (node (ref "CC_C14") (pin "2") (pinfunction "2_2") (pintype "passive"))
      (node (ref "CC_C20") (pin "2") (pinfunction "2_2") (pintype "passive"))
      (node (ref "CC_C8") (pin "2") (pinfunction "2_2") (pintype "passive"))
      (node (ref "CC_CX1") (pin "2") (pinfunction "2_2") (pintype "passive"))
      (node (ref "CC_CX2") (pin "2") (pinfunction "2_2") (pintype "passive"))
      (node (ref "CC_DCOUP") (pin "2") (pinfunction "2_2") (pintype "passive"))
      (node (ref "ESP-C1") (pin "2") (pinfunction "2_2") (pintype "passive"))
      (node (ref "ESP-GPIO0") (pin "3") (pinfunction "3_3") (pintype "passive"))
      (node (ref "ETH-C1") (pin "1") (pinfunction "1_1") (pintype "passive"))
      (node (ref "ETH-C3") (pin "1") (pinfunction "1_1") (pintype "passive"))
      (node (ref "IC1") (pin "P$17") (pinfunction "GND_P$17") (pintype "power_in"))
      (node (ref "IC1") (pin "P$18") (pinfunction "GND_P$18") (pintype "power_in"))
      (node (ref "IC1") (pin "P$29") (pinfunction "GND_P$29") (pintype "power_in"))
      (node (ref "IC1") (pin "P$39") (pinfunction "GND_P$39") (pintype "power_in"))
      (node (ref "IC1") (pin "P$45") (pinfunction "GND_P$45") (pintype "power_in"))
      (node (ref "IC1") (pin "P$46") (pinfunction "GND_P$46") (pintype "power_in"))
      (node (ref "IC1") (pin "P$53") (pinfunction "GND_P$53") (pintype "power_in"))
      (node (ref "IC1") (pin "P$54") (pinfunction "GND_P$54") (pintype "power_in"))
      (node (ref "IC1") (pin "P$58") (pinfunction "GND_P$58") (pintype "power_in"))
      (node (ref "IC1") (pin "P$59") (pinfunction "GND_P$59") (pintype "power_in"))
      (node (ref "IC1") (pin "P$61") (pinfunction "GND_P$61") (pintype "power_in"))
      (node (ref "IC1") (pin "P$62") (pinfunction "GND_P$62") (pintype "power_in"))
      (node (ref "IC1") (pin "P$63") (pinfunction "GND_P$63") (pintype "power_in"))
      (node (ref "IC1") (pin "P$64") (pinfunction "GND_P$64") (pintype "power_in"))
      (node (ref "IC1") (pin "P$65") (pinfunction "GND_P$65") (pintype "power_in"))
      (node (ref "IC2") (pin "13") (pinfunction "G_13") (pintype "input"))
      (node (ref "IC2") (pin "8") (pinfunction "GND_8") (pintype "power_in"))
      (node (ref "IC3") (pin "13") (pinfunction "G_13") (pintype "input"))
      (node (ref "IC3") (pin "8") (pinfunction "GND_8") (pintype "power_in"))
      (node (ref "IC4") (pin "2") (pinfunction "DGND_2") (pintype "power_in"))
      (node (ref "IC4") (pin "21") (pinfunction "CS_21") (pintype "input"))
      (node (ref "IC5") (pin "13") (pinfunction "G_13") (pintype "input"))
      (node (ref "IC5") (pin "8") (pinfunction "GND_8") (pintype "power_in"))
      (node (ref "J1") (pin "P$1") (pinfunction "GND_P$1") (pintype "bidirectional"))
      (node (ref "J1") (pin "P$2") (pinfunction "GND_P$2") (pintype "bidirectional"))
      (node (ref "MQ2-R1") (pin "1") (pinfunction "1_1") (pintype "passive"))
      (node (ref "RBIAS") (pin "2") (pinfunction "2_2") (pintype "passive"))
      (node (ref "RW5500-1") (pin "1") (pinfunction "1_1") (pintype "passive"))
      (node (ref "RW5500-2") (pin "5") (pinfunction "2_5") (pintype "passive"))
      (node (ref "RW5500-2") (pin "6") (pinfunction "2_6") (pintype "passive"))
      (node (ref "RW5500-2") (pin "7") (pinfunction "2_7") (pintype "passive"))
      (node (ref "RW5500-2") (pin "8") (pinfunction "2_8") (pintype "passive"))
      (node (ref "S1") (pin "3") (pinfunction "3_3") (pintype "passive"))
      (node (ref "S1") (pin "4") (pinfunction "4_4") (pintype "passive"))
      (node (ref "SENSOR-MQ2") (pin "HB") (pinfunction "HB_HB") (pintype "bidirectional"))
      (node (ref "SIM900-C1") (pin "-") (pinfunction "-_-") (pintype "passive"))
      (node (ref "SIM900-C2") (pin "-") (pinfunction "-_-") (pintype "passive"))
      (node (ref "SIM900-C3") (pin "2") (pinfunction "2_2") (pintype "passive"))
      (node (ref "SIM900-C4") (pin "2") (pinfunction "2_2") (pintype "passive"))
      (node (ref "SIM900-C5") (pin "2") (pinfunction "2_2") (pintype "passive"))
      (node (ref "SIM900-R6") (pin "2") (pinfunction "2_2") (pintype "passive"))
      (node (ref "SIM900-R9") (pin "2") (pinfunction "2_2") (pintype "passive"))
      (node (ref "SIM900-T1") (pin "E") (pinfunction "E_E") (pintype "passive"))
      (node (ref "SIM900-T2") (pin "E") (pinfunction "E_E") (pintype "passive"))
      (node (ref "SIM900-T3") (pin "E") (pinfunction "E_E") (pintype "passive"))
      (node (ref "SIM_C1") (pin "1") (pinfunction "1_1") (pintype "passive"))
      (node (ref "SIM_C2") (pin "1") (pinfunction "1_1") (pintype "passive"))
      (node (ref "SR_OUT1") (pin "2") (pinfunction "2_2") (pintype "passive"))
      (node (ref "SR_OUT2") (pin "2") (pinfunction "2_2") (pintype "passive"))
      (node (ref "STM-C1") (pin "1") (pinfunction "1_1") (pintype "passive"))
      (node (ref "STM-C10") (pin "2") (pinfunction "2_2") (pintype "passive"))
      (node (ref "STM-C11") (pin "2") (pinfunction "2_2") (pintype "passive"))
      (node (ref "STM-C12") (pin "2") (pinfunction "2_2") (pintype "passive"))
      (node (ref "STM-C13") (pin "2") (pinfunction "2_2") (pintype "passive"))
      (node (ref "STM-C2") (pin "1") (pinfunction "1_1") (pintype "passive"))
      (node (ref "STM-C3") (pin "1") (pinfunction "1_1") (pintype "passive"))
      (node (ref "STM-C8") (pin "2") (pinfunction "2_2") (pintype "passive"))
      (node (ref "STM-SWD") (pin "3") (pinfunction "3_3") (pintype "passive"))
      (node (ref "STM-USART") (pin "4") (pinfunction "4_4") (pintype "passive"))
      (node (ref "STM_CHIP") (pin "18") (pinfunction "VSS_4_18") (pintype "power_in"))
      (node (ref "STM_CHIP") (pin "31") (pinfunction "VSS_1_31") (pintype "power_in"))
      (node (ref "STM_CHIP") (pin "47") (pinfunction "VSS_2_47") (pintype "power_in"))
      (node (ref "STM_CHIP") (pin "63") (pinfunction "VSS_3_63") (pintype "power_in"))
      (node (ref "SYS-C1") (pin "2") (pinfunction "2_2") (pintype "passive"))
      (node (ref "SYS-C3") (pin "2") (pinfunction "2_2") (pintype "passive"))
      (node (ref "SYS-L1") (pin "2") (pinfunction "2_2") (pintype "passive"))
      (node (ref "U$13") (pin "LCD_GND") (pinfunction "LCD_GND_LCD_GND") (pintype "power_in"))
      (node (ref "U$13") (pin "T_CS") (pinfunction "T_CS_T_CS") (pintype "bidirectional"))
      (node (ref "U$14") (pin "SHIELD$1") (pinfunction "P$5_SHIELD$1") (pintype "bidirectional"))
      (node (ref "U$14") (pin "SHIELD$2") (pinfunction "P$6_SHIELD$2") (pintype "bidirectional"))
      (node (ref "U$15") (pin "SHIELD$1") (pinfunction "P$5_SHIELD$1") (pintype "bidirectional"))
      (node (ref "U$15") (pin "SHIELD$2") (pinfunction "P$6_SHIELD$2") (pintype "bidirectional"))
      (node (ref "U$16") (pin "SHIELD$1") (pinfunction "P$5_SHIELD$1") (pintype "bidirectional"))
      (node (ref "U$16") (pin "SHIELD$2") (pinfunction "P$6_SHIELD$2") (pintype "bidirectional"))
      (node (ref "U$17") (pin "GND") (pinfunction "GND_GND") (pintype "bidirectional"))
      (node (ref "U$3") (pin "GND") (pinfunction "GND_GND") (pintype "bidirectional"))
      (node (ref "U$4") (pin "3") (pinfunction "CS_3") (pintype "input"))
      (node (ref "U$5") (pin "GND") (pinfunction "GND_GND") (pintype "bidirectional"))
      (node (ref "U$5") (pin "GPIO15") (pinfunction "GPIO15_GPIO15") (pintype "bidirectional"))
      (node (ref "U$6") (pin "GND$1") (pinfunction "GNDI_GND$1") (pintype "bidirectional"))
      (node (ref "U$6") (pin "GND$2") (pinfunction "GNDO_GND$2") (pintype "bidirectional"))
      (node (ref "U$7") (pin "P$1") (pinfunction "GND_P$1") (pintype "bidirectional"))
      (node (ref "U$7") (pin "P$2") (pinfunction "GND_P$2") (pintype "bidirectional"))
      (node (ref "U$8") (pin "SHIELD_GND$1") (pinfunction "GND$1_SHIELD_GND$1") (pintype "bidirectional"))
      (node (ref "U$8") (pin "SHIELD_GND$2") (pinfunction "GND$2_SHIELD_GND$2") (pintype "bidirectional"))
      (node (ref "U$8") (pin "SIM_GND") (pinfunction "SIM_GND_SIM_GND") (pintype "bidirectional"))
      (node (ref "U2") (pin "14") (pinfunction "AGND_14") (pintype "passive"))
      (node (ref "U2") (pin "16") (pinfunction "AGND_16") (pintype "passive"))
      (node (ref "U2") (pin "19") (pinfunction "AGND_19") (pintype "passive"))
      (node (ref "U2") (pin "29") (pinfunction "GND_29") (pintype "passive"))
      (node (ref "U2") (pin "3") (pinfunction "AGND_3") (pintype "passive"))
      (node (ref "U2") (pin "48") (pinfunction "AGND_48") (pintype "passive"))
      (node (ref "U2") (pin "9") (pinfunction "AGND_9") (pintype "passive"))
      (node (ref "USB_IN") (pin "GND1") (pinfunction "GND_GND1") (pintype "bidirectional"))
      (node (ref "USB_IN") (pin "SHIELD1") (pinfunction "SHIELD_SHIELD1") (pintype "bidirectional"))
      (node (ref "USB_IN") (pin "SHIELD2") (pinfunction "SHIELD_SHIELD2") (pintype "bidirectional"))
      (node (ref "USB_IN") (pin "SHIELD3") (pinfunction "SHIELD_SHIELD3") (pintype "bidirectional"))
      (node (ref "W5500-C1") (pin "2") (pinfunction "2_2") (pintype "passive"))
      (node (ref "W5500-C10") (pin "2") (pinfunction "2_2") (pintype "passive"))
      (node (ref "W5500-C11") (pin "2") (pinfunction "2_2") (pintype "passive"))
      (node (ref "W5500-C12") (pin "-") (pinfunction "-_-") (pintype "passive"))
      (node (ref "W5500-C13") (pin "-") (pinfunction "-_-") (pintype "passive"))
      (node (ref "W5500-C2") (pin "2") (pinfunction "2_2") (pintype "passive"))
      (node (ref "W5500-C3") (pin "2") (pinfunction "2_2") (pintype "passive"))
      (node (ref "W5500-C4") (pin "2") (pinfunction "2_2") (pintype "passive"))
      (node (ref "W5500-C5") (pin "2") (pinfunction "2_2") (pintype "passive"))
      (node (ref "W5500-C6") (pin "2") (pinfunction "2_2") (pintype "passive"))
      (node (ref "W5500-C7") (pin "2") (pinfunction "2_2") (pintype "passive"))
      (node (ref "W5500-C8") (pin "2") (pinfunction "2_2") (pintype "passive"))
      (node (ref "W5500-C9") (pin "2") (pinfunction "2_2") (pintype "passive"))
      (node (ref "W5500-R11") (pin "1") (pinfunction "1_1") (pintype "passive"))
      (node (ref "W5500-R12") (pin "1") (pinfunction "1_1") (pintype "passive"))
    )
    (net (code "37") (name "DHT_DATA") (class "Default")
      (node (ref "DHT-R1") (pin "2") (pinfunction "2_2") (pintype "passive"))
      (node (ref "STM_CHIP") (pin "54") (pinfunction "PD2_54") (pintype "bidirectional"))
      (node (ref "U$17") (pin "DATA") (pinfunction "DATA_DATA") (pintype "bidirectional"))
    )
    (net (code "38") (name "ESP_GPIO0") (class "Default")
      (node (ref "ESP-GPIO0") (pin "2") (pinfunction "2_2") (pintype "passive"))
      (node (ref "U$5") (pin "GPIO00") (pinfunction "GPIO0_GPIO00") (pintype "bidirectional"))
    )
    (net (code "39") (name "ESP_RX") (class "Default")
      (node (ref "ESP_EXT") (pin "3") (pinfunction "3_3") (pintype "passive"))
      (node (ref "JP_ESP_RX") (pin "1") (pinfunction "1_1") (pintype "passive"))
      (node (ref "U$5") (pin "RXD") (pinfunction "RXD_RXD") (pintype "bidirectional"))
    )
    (net (code "40") (name "ESP_TX") (class "Default")
      (node (ref "ESP_EXT") (pin "4") (pinfunction "4_4") (pintype "passive"))
      (node (ref "JP_ESP_TX") (pin "1") (pinfunction "1_1") (pintype "passive"))
      (node (ref "U$5") (pin "TXD") (pinfunction "TXD_TXD") (pintype "bidirectional"))
    )
    (net (code "41") (name "ETH_CS") (class "Default")
      (node (ref "STM_CHIP") (pin "33") (pinfunction "PB12_33") (pintype "bidirectional"))
      (node (ref "U2") (pin "32") (pinfunction "SCS_N_32") (pintype "passive"))
      (node (ref "W5500-R13") (pin "1") (pinfunction "1_1") (pintype "passive"))
    )
    (net (code "42") (name "ETH_MISO") (class "Default")
      (node (ref "STM_CHIP") (pin "35") (pinfunction "PB14_35") (pintype "bidirectional"))
      (node (ref "U2") (pin "34") (pinfunction "MISO_34") (pintype "passive"))
    )
    (net (code "43") (name "ETH_MOSI") (class "Default")
      (node (ref "STM_CHIP") (pin "36") (pinfunction "PB15_36") (pintype "bidirectional"))
      (node (ref "U2") (pin "35") (pinfunction "MOSI_35") (pintype "passive"))
    )
    (net (code "44") (name "ETH_RSTN") (class "Default")
      (node (ref "RW5500-3") (pin "2") (pinfunction "2_2") (pintype "passive"))
      (node (ref "STM_CHIP") (pin "37") (pinfunction "PC6_37") (pintype "bidirectional"))
      (node (ref "U2") (pin "37") (pinfunction "RST_N_37") (pintype "passive"))
    )
    (net (code "45") (name "ETH_SCK") (class "Default")
      (node (ref "STM_CHIP") (pin "34") (pinfunction "PB13_34") (pintype "bidirectional"))
      (node (ref "U2") (pin "33") (pinfunction "SCLK_33") (pintype "passive"))
    )
    (net (code "46") (name "LCD_CS") (class "Default")
      (node (ref "STM_CHIP") (pin "20") (pinfunction "PA4_20") (pintype "bidirectional"))
      (node (ref "U$13") (pin "LCD_CS") (pinfunction "LCD_CS_LCD_CS") (pintype "bidirectional"))
    )
    (net (code "47") (name "LCD_D{slash}C") (class "Default")
      (node (ref "STM_CHIP") (pin "24") (pinfunction "PC4_24") (pintype "bidirectional"))
      (node (ref "U$13") (pin "LCD_D/C") (pinfunction "LCD_D/C_LCD_D/C") (pintype "bidirectional"))
    )
    (net (code "48") (name "LCD_LED") (class "Default")
      (node (ref "LCD-R1") (pin "1") (pinfunction "1_1") (pintype "passive"))
      (node (ref "U$13") (pin "LED") (pinfunction "LCD_LED_LED") (pintype "bidirectional"))
    )
    (net (code "49") (name "LCD_MISO") (class "Default")
      (node (ref "STM_CHIP") (pin "22") (pinfunction "PA6_22") (pintype "bidirectional"))
      (node (ref "U$13") (pin "LCD_MISO") (pinfunction "LCD_MISO_LCD_MISO") (pintype "bidirectional"))
      (node (ref "U$13") (pin "SD_MISO") (pinfunction "SD_MISO_SD_MISO") (pintype "bidirectional"))
    )
    (net (code "50") (name "LCD_MOSI") (class "Default")
      (node (ref "STM_CHIP") (pin "23") (pinfunction "PA7_23") (pintype "bidirectional"))
      (node (ref "U$13") (pin "LCD_MOSI") (pinfunction "LCD_MOSI_LCD_MOSI") (pintype "bidirectional"))
      (node (ref "U$13") (pin "SD_MOSI") (pinfunction "SD_MOSI_SD_MOSI") (pintype "bidirectional"))
    )
    (net (code "51") (name "LCD_RESET") (class "Default")
      (node (ref "STM_CHIP") (pin "25") (pinfunction "PC5_25") (pintype "bidirectional"))
      (node (ref "U$13") (pin "LCD_RESET") (pinfunction "LCD_RESET_LCD_RESET") (pintype "bidirectional"))
    )
    (net (code "52") (name "LCD_SCK") (class "Default")
      (node (ref "STM_CHIP") (pin "21") (pinfunction "PA5_21") (pintype "bidirectional"))
      (node (ref "U$13") (pin "LCD_SCK") (pinfunction "LCD_SCK_LCD_SCK") (pintype "bidirectional"))
      (node (ref "U$13") (pin "SD_SCK") (pinfunction "SD_SCK_SD_SCK") (pintype "bidirectional"))
    )
    (net (code "53") (name "LINKLED") (class "Default")
      (node (ref "ETH-R5") (pin "1") (pinfunction "1_1") (pintype "passive"))
      (node (ref "U2") (pin "25") (pinfunction "LINKLED_25") (pintype "passive"))
    )
    (net (code "54") (name "MQ2_DATA") (class "Default")
      (node (ref "MQ2-R1") (pin "2") (pinfunction "2_2") (pintype "passive"))
      (node (ref "SENSOR-MQ2") (pin "B1") (pinfunction "B1_B1") (pintype "bidirectional"))
      (node (ref "SENSOR-MQ2") (pin "B2") (pinfunction "B2_B2") (pintype "bidirectional"))
      (node (ref "STM_CHIP") (pin "26") (pinfunction "PB0_26") (pintype "bidirectional"))
    )
    (net (code "55") (name "N") (class "Default")
      (node (ref "U$10") (pin "IB") (pinfunction "IB_IB") (pintype "bidirectional"))
      (node (ref "U$11") (pin "IB") (pinfunction "IB_IB") (pintype "bidirectional"))
      (node (ref "U$12") (pin "PIN$4") (pinfunction "P$4_PIN$4") (pintype "bidirectional"))
      (node (ref "U$3") (pin "AC$2") (pinfunction "AC_IN$2_AC$2") (pintype "bidirectional"))
      (node (ref "U$9") (pin "IB") (pinfunction "IB_IB") (pintype "bidirectional"))
    )
    (net (code "56") (name "Net-(ADE-R1-Pad1)") (class "Default")
      (node (ref "ADE-R1") (pin "1") (pinfunction "1_1") (pintype "passive"))
      (node (ref "RTO1") (pin "2") (pinfunction "2_2") (pintype "passive"))
      (node (ref "U$9") (pin "OA") (pinfunction "OA_OA") (pintype "bidirectional"))
    )
    (net (code "57") (name "Net-(ADE-R2-Pad1)") (class "Default")
      (node (ref "ADE-R2") (pin "1") (pinfunction "1_1") (pintype "passive"))
      (node (ref "RTO2") (pin "2") (pinfunction "2_2") (pintype "passive"))
      (node (ref "U$10") (pin "OA") (pinfunction "OA_OA") (pintype "bidirectional"))
    )
    (net (code "58") (name "Net-(ADE-R3-Pad1)") (class "Default")
      (node (ref "ADE-R3") (pin "1") (pinfunction "1_1") (pintype "passive"))
      (node (ref "RTO3") (pin "2") (pinfunction "2_2") (pintype "passive"))
      (node (ref "U$11") (pin "OA") (pinfunction "OA_OA") (pintype "bidirectional"))
    )
    (net (code "59") (name "Net-(ADE-R7-Pad1)") (class "Default")
      (node (ref "ADE-R7") (pin "1") (pinfunction "1_1") (pintype "passive"))
      (node (ref "RTO1") (pin "1") (pinfunction "1_1") (pintype "passive"))
      (node (ref "RTO2") (pin "1") (pinfunction "1_1") (pintype "passive"))
      (node (ref "RTO3") (pin "1") (pinfunction "1_1") (pintype "passive"))
      (node (ref "U$10") (pin "OB") (pinfunction "OB_OB") (pintype "bidirectional"))
      (node (ref "U$11") (pin "OB") (pinfunction "OB_OB") (pintype "bidirectional"))
      (node (ref "U$9") (pin "OB") (pinfunction "OB_OB") (pintype "bidirectional"))
    )
    (net (code "60") (name "Net-(ADE-R8-Pad2)") (class "Default")
      (node (ref "ADE-R8") (pin "2") (pinfunction "2_2") (pintype "passive"))
      (node (ref "ADE-R9") (pin "1") (pinfunction "1_1") (pintype "passive"))
      (node (ref "U$14") (pin "P$3") (pinfunction "P$3_P$3") (pintype "bidirectional"))
      (node (ref "U$14") (pin "P$4") (pinfunction "P$4_P$4") (pintype "bidirectional"))
    )
    (net (code "61") (name "Net-(ADE-R10-Pad1)") (class "Default")
      (node (ref "ADE-R10") (pin "1") (pinfunction "1_1") (pintype "passive"))
      (node (ref "ADE-R8") (pin "1") (pinfunction "1_1") (pintype "passive"))
      (node (ref "U$14") (pin "P$1") (pinfunction "P$1_P$1") (pintype "bidirectional"))
      (node (ref "U$14") (pin "P$2") (pinfunction "P$2_P$2") (pintype "bidirectional"))
    )
    (net (code "62") (name "Net-(ADE-R11-Pad1)") (class "Default")
      (node (ref "ADE-R11") (pin "1") (pinfunction "1_1") (pintype "passive"))
      (node (ref "ADE-R13") (pin "1") (pinfunction "1_1") (pintype "passive"))
      (node (ref "U$15") (pin "P$1") (pinfunction "P$1_P$1") (pintype "bidirectional"))
      (node (ref "U$15") (pin "P$2") (pinfunction "P$2_P$2") (pintype "bidirectional"))
    )
    (net (code "63") (name "Net-(ADE-R11-Pad2)") (class "Default")
      (node (ref "ADE-R11") (pin "2") (pinfunction "2_2") (pintype "passive"))
      (node (ref "ADE-R12") (pin "1") (pinfunction "1_1") (pintype "passive"))
      (node (ref "U$15") (pin "P$3") (pinfunction "P$3_P$3") (pintype "bidirectional"))
      (node (ref "U$15") (pin "P$4") (pinfunction "P$4_P$4") (pintype "bidirectional"))
    )
    (net (code "64") (name "Net-(ADE-R14-Pad1)") (class "Default")
      (node (ref "ADE-R14") (pin "1") (pinfunction "1_1") (pintype "passive"))
      (node (ref "ADE-R16") (pin "1") (pinfunction "1_1") (pintype "passive"))
      (node (ref "U$16") (pin "P$1") (pinfunction "P$1_P$1") (pintype "bidirectional"))
      (node (ref "U$16") (pin "P$2") (pinfunction "P$2_P$2") (pintype "bidirectional"))
    )
    (net (code "65") (name "Net-(ADE-R14-Pad2)") (class "Default")
      (node (ref "ADE-R14") (pin "2") (pinfunction "2_2") (pintype "passive"))
      (node (ref "ADE-R15") (pin "1") (pinfunction "1_1") (pintype "passive"))
      (node (ref "U$16") (pin "P$3") (pinfunction "P$3_P$3") (pintype "bidirectional"))
      (node (ref "U$16") (pin "P$4") (pinfunction "P$4_P$4") (pintype "bidirectional"))
    )
    (net (code "66") (name "Net-(B1-ANT)") (class "Default")
      (node (ref "B1") (pin "1") (pinfunction "ANT_1") (pintype "bidirectional"))
      (node (ref "J1") (pin "P$3") (pinfunction "SIGNAL_P$3") (pintype "bidirectional"))
    )
    (net (code "67") (name "Net-(B1-BAL_N)") (class "Default")
      (node (ref "B1") (pin "3") (pinfunction "BAL_N_3") (pintype "bidirectional"))
      (node (ref "U$4") (pin "19") (pinfunction "RF-N_19") (pintype "bidirectional"))
    )
    (net (code "68") (name "Net-(B1-BAL_P)") (class "Default")
      (node (ref "B1") (pin "4") (pinfunction "BAL_P_4") (pintype "bidirectional"))
      (node (ref "U$4") (pin "17") (pinfunction "RF-P_17") (pintype "bidirectional"))
    )
    (net (code "69") (name "Net-(ETHERNET-LED1_K)") (class "Default")
      (node (ref "ETH-R4") (pin "2") (pinfunction "2_2") (pintype "passive"))
      (node (ref "ETHERNET") (pin "10") (pinfunction "LED1_K_10") (pintype "bidirectional"))
    )
    (net (code "70") (name "Net-(ETHERNET-LED2_K)") (class "Default")
      (node (ref "ETH-R5") (pin "2") (pinfunction "2_2") (pintype "passive"))
      (node (ref "ETHERNET") (pin "11") (pinfunction "LED2_K_11") (pintype "bidirectional"))
    )
    (net (code "71") (name "Net-(ETHERNET-RCT)") (class "Default")
      (node (ref "ETH-C3") (pin "2") (pinfunction "2_2") (pintype "passive"))
      (node (ref "ETH-R6") (pin "1") (pinfunction "1_1") (pintype "passive"))
      (node (ref "ETH-R7") (pin "2") (pinfunction "2_2") (pintype "passive"))
      (node (ref "ETHERNET") (pin "6") (pinfunction "RCT_6") (pintype "bidirectional"))
    )
    (net (code "72") (name "Net-(ETHERNET-RX+)") (class "Default")
      (node (ref "ETH-C2") (pin "1") (pinfunction "1_1") (pintype "passive"))
      (node (ref "ETHERNET") (pin "7") (pinfunction "RX+_7") (pintype "bidirectional"))
    )
    (net (code "73") (name "Net-(ETHERNET-RX-)") (class "Default")
      (node (ref "ETH-C4") (pin "1") (pinfunction "1_1") (pintype "passive"))
      (node (ref "ETHERNET") (pin "8") (pinfunction "RX-_8") (pintype "bidirectional"))
    )
    (net (code "74") (name "Net-(ETHERNET-TCT)") (class "Default")
      (node (ref "ETH-C1") (pin "2") (pinfunction "2_2") (pintype "passive"))
      (node (ref "ETH-R3") (pin "1") (pinfunction "1_1") (pintype "passive"))
      (node (ref "ETHERNET") (pin "3") (pinfunction "TCT_3") (pintype "bidirectional"))
    )
    (net (code "75") (name "Net-(IC1-RF_ANT)") (class "Default")
      (node (ref "IC1") (pin "P$60") (pinfunction "RF_ANT_P$60") (pintype "bidirectional"))
      (node (ref "U$7") (pin "P$3") (pinfunction "SIGNAL_P$3") (pintype "bidirectional"))
    )
    (net (code "76") (name "Net-(IC1-SIM_CLK)") (class "Default")
      (node (ref "IC1") (pin "P$32") (pinfunction "SIM_CLK_P$32") (pintype "bidirectional"))
      (node (ref "SIM900-R2") (pin "1") (pinfunction "1_1") (pintype "passive"))
    )
    (net (code "77") (name "Net-(IC1-SIM_DATA)") (class "Default")
      (node (ref "IC1") (pin "P$31") (pinfunction "SIM_DATA_P$31") (pintype "bidirectional"))
      (node (ref "SIM900-R3") (pin "1") (pinfunction "1_1") (pintype "passive"))
    )
    (net (code "78") (name "Net-(IC1-SIM_RST)") (class "Default")
      (node (ref "IC1") (pin "P$33") (pinfunction "SIM_RST_P$33") (pintype "bidirectional"))
      (node (ref "SIM900-R1") (pin "1") (pinfunction "1_1") (pintype "passive"))
    )
    (net (code "79") (name "Net-(IC1-VBAT1)") (class "Default")
      (node (ref "IC1") (pin "P$55") (pinfunction "VBAT1_P$55") (pintype "power_in"))
      (node (ref "IC1") (pin "P$56") (pinfunction "VBAT2_P$56") (pintype "power_in"))
      (node (ref "IC1") (pin "P$57") (pinfunction "VBAT3_P$57") (pintype "power_in"))
      (node (ref "SIM900-C1") (pin "+") (pinfunction "+_+") (pintype "passive"))
      (node (ref "SIM900-C2") (pin "+") (pinfunction "+_+") (pintype "passive"))
      (node (ref "SYS-L2") (pin "1") (pinfunction "1_1") (pintype "passive"))
    )
    (net (code "80") (name "Net-(IC1-VRTC)") (class "Default")
      (node (ref "IC1") (pin "P$26") (pinfunction "VRTC_P$26") (pintype "power_in"))
      (node (ref "SIM900-C3") (pin "1") (pinfunction "1_1") (pintype "passive"))
    )
    (net (code "81") (name "Net-(IC4A-CLKIN)") (class "Default")
      (node (ref "ADE-C3") (pin "1") (pinfunction "1_1") (pintype "passive"))
      (node (ref "ADE-XTAL") (pin "1") (pinfunction "1_1") (pintype "passive"))
      (node (ref "IC4") (pin "19") (pinfunction "CLKIN_19") (pintype "input"))
    )
    (net (code "82") (name "Net-(IC4A-CLKOUT)") (class "Default")
      (node (ref "ADE-C4") (pin "1") (pinfunction "1_1") (pintype "passive"))
      (node (ref "ADE-XTAL") (pin "2") (pinfunction "2_2") (pintype "passive"))
      (node (ref "IC4") (pin "20") (pinfunction "CLKOUT_20") (pintype "output"))
    )
    (net (code "83") (name "Net-(IC4C-IN)") (class "Default")
      (node (ref "ADE-C12") (pin "1") (pinfunction "1_1") (pintype "passive"))
      (node (ref "ADE-R10") (pin "2") (pinfunction "2_2") (pintype "passive"))
      (node (ref "IC4") (pin "6") (pinfunction "IN_6") (pintype "input"))
    )
    (net (code "84") (name "Net-(IC4C-IP)") (class "Default")
      (node (ref "ADE-C11") (pin "1") (pinfunction "1_1") (pintype "passive"))
      (node (ref "ADE-R9") (pin "2") (pinfunction "2_2") (pintype "passive"))
      (node (ref "IC4") (pin "5") (pinfunction "IP_5") (pintype "input"))
    )
    (net (code "85") (name "Net-(IC4D-IN)") (class "Default")
      (node (ref "ADE-C14") (pin "1") (pinfunction "1_1") (pintype "passive"))
      (node (ref "ADE-R13") (pin "2") (pinfunction "2_2") (pintype "passive"))
      (node (ref "IC4") (pin "8") (pinfunction "IN_8") (pintype "input"))
    )
    (net (code "86") (name "Net-(IC4D-IP)") (class "Default")
      (node (ref "ADE-C13") (pin "1") (pinfunction "1_1") (pintype "passive"))
      (node (ref "ADE-R12") (pin "2") (pinfunction "2_2") (pintype "passive"))
      (node (ref "IC4") (pin "7") (pinfunction "IP_7") (pintype "input"))
    )
    (net (code "87") (name "Net-(IC4E-IN)") (class "Default")
      (node (ref "ADE-C16") (pin "1") (pinfunction "1_1") (pintype "passive"))
      (node (ref "ADE-R16") (pin "2") (pinfunction "2_2") (pintype "passive"))
      (node (ref "IC4") (pin "10") (pinfunction "IN_10") (pintype "input"))
    )
    (net (code "88") (name "Net-(IC4E-IP)") (class "Default")
      (node (ref "ADE-C15") (pin "1") (pinfunction "1_1") (pintype "passive"))
      (node (ref "ADE-R15") (pin "2") (pinfunction "2_2") (pintype "passive"))
      (node (ref "IC4") (pin "9") (pinfunction "IP_9") (pintype "input"))
    )
    (net (code "89") (name "Net-(IC4F-REF)") (class "Default")
      (node (ref "ADE-C1") (pin "1") (pinfunction "1_1") (pintype "passive"))
      (node (ref "ADE-C2") (pin "1") (pinfunction "1_1") (pintype "passive"))
      (node (ref "IC4") (pin "12") (pinfunction "REF_12") (pintype "bidirectional"))
    )
    (net (code "90") (name "Net-(IC4G-VAP)") (class "Default")
      (node (ref "ADE-C7") (pin "1") (pinfunction "1_1") (pintype "passive"))
      (node (ref "ADE-R1") (pin "2") (pinfunction "2_2") (pintype "passive"))
      (node (ref "ADE-R4") (pin "2") (pinfunction "2_2") (pintype "passive"))
      (node (ref "IC4") (pin "16") (pinfunction "VAP_16") (pintype "input"))
    )
    (net (code "91") (name "Net-(IC4G-VBP)") (class "Default")
      (node (ref "ADE-C8") (pin "1") (pinfunction "1_1") (pintype "passive"))
      (node (ref "ADE-R2") (pin "2") (pinfunction "2_2") (pintype "passive"))
      (node (ref "ADE-R5") (pin "2") (pinfunction "2_2") (pintype "passive"))
      (node (ref "IC4") (pin "15") (pinfunction "VBP_15") (pintype "input"))
    )
    (net (code "92") (name "Net-(IC4G-VCP)") (class "Default")
      (node (ref "ADE-C9") (pin "1") (pinfunction "1_1") (pintype "passive"))
      (node (ref "ADE-R3") (pin "2") (pinfunction "2_2") (pintype "passive"))
      (node (ref "ADE-R6") (pin "2") (pinfunction "2_2") (pintype "passive"))
      (node (ref "IC4") (pin "14") (pinfunction "VCP_14") (pintype "input"))
    )
    (net (code "93") (name "Net-(IC4G-VN)") (class "Default")
      (node (ref "ADE-C10") (pin "1") (pinfunction "1_1") (pintype "passive"))
      (node (ref "ADE-R7") (pin "2") (pinfunction "2_2") (pintype "passive"))
      (node (ref "IC4") (pin "13") (pinfunction "VN_13") (pintype "input"))
    )
    (net (code "94") (name "Net-(OK1A-A)") (class "Default")
      (node (ref "OK1") (pin "1") (pinfunction "A_1") (pintype "passive"))
      (node (ref "R_CH3") (pin "2") (pinfunction "2_2") (pintype "passive"))
    )
    (net (code "95") (name "Net-(OK1B-A)") (class "Default")
      (node (ref "OK1") (pin "3") (pinfunction "A_3") (pintype "passive"))
      (node (ref "R_CH4") (pin "2") (pinfunction "2_2") (pintype "passive"))
    )
    (net (code "96") (name "Net-(OK2A-A)") (class "Default")
      (node (ref "OK2") (pin "1") (pinfunction "A_1") (pintype "passive"))
      (node (ref "R_CH1") (pin "2") (pinfunction "2_2") (pintype "passive"))
    )
    (net (code "97") (name "Net-(OK2B-A)") (class "Default")
      (node (ref "OK2") (pin "3") (pinfunction "A_3") (pintype "passive"))
      (node (ref "R_CH2") (pin "2") (pinfunction "2_2") (pintype "passive"))
    )
    (net (code "98") (name "Net-(RT1-Pad2)") (class "Default")
      (node (ref "RT1") (pin "2") (pinfunction "2_2") (pintype "passive"))
      (node (ref "U$9") (pin "IA") (pinfunction "IA_IA") (pintype "bidirectional"))
    )
    (net (code "99") (name "Net-(RT2-Pad2)") (class "Default")
      (node (ref "RT2") (pin "2") (pinfunction "2_2") (pintype "passive"))
      (node (ref "U$10") (pin "IA") (pinfunction "IA_IA") (pintype "bidirectional"))
    )
    (net (code "100") (name "Net-(RT3-Pad2)") (class "Default")
      (node (ref "RT3") (pin "2") (pinfunction "2_2") (pintype "passive"))
      (node (ref "U$11") (pin "IA") (pinfunction "IA_IA") (pintype "bidirectional"))
    )
    (net (code "101") (name "Net-(RW5500-1A-2)") (class "Default")
      (node (ref "RW5500-1") (pin "8") (pinfunction "2_8") (pintype "passive"))
      (node (ref "U2") (pin "42") (pinfunction "RSVD_42") (pintype "passive"))
    )
    (net (code "102") (name "Net-(RW5500-1B-2)") (class "Default")
      (node (ref "RW5500-1") (pin "7") (pinfunction "2_7") (pintype "passive"))
      (node (ref "U2") (pin "43") (pinfunction "PMODE2_43") (pintype "passive"))
    )
    (net (code "103") (name "Net-(RW5500-1C-2)") (class "Default")
      (node (ref "RW5500-1") (pin "6") (pinfunction "2_6") (pintype "passive"))
      (node (ref "U2") (pin "44") (pinfunction "PMODE1_44") (pintype "passive"))
    )
    (net (code "104") (name "Net-(RW5500-1D-2)") (class "Default")
      (node (ref "RW5500-1") (pin "5") (pinfunction "2_5") (pintype "passive"))
      (node (ref "U2") (pin "45") (pinfunction "PMODE0_45") (pintype "passive"))
    )
    (net (code "105") (name "Net-(RW5500-2-Pad1)") (class "Default")
      (node (ref "RW5500-2") (pin "1") (pinfunction "1_1") (pintype "passive"))
      (node (ref "U2") (pin "41") (pinfunction "RSVD_41") (pintype "passive"))
    )
    (net (code "106") (name "Net-(RW5500-2B-1)") (class "Default")
      (node (ref "RW5500-2") (pin "2") (pinfunction "1_2") (pintype "passive"))
      (node (ref "U2") (pin "40") (pinfunction "RSVD_40") (pintype "passive"))
    )
    (net (code "107") (name "Net-(RW5500-2C-1)") (class "Default")
      (node (ref "RW5500-2") (pin "3") (pinfunction "1_3") (pintype "passive"))
      (node (ref "U2") (pin "39") (pinfunction "RSVD_39") (pintype "passive"))
    )
    (net (code "108") (name "Net-(RW5500-2D-1)") (class "Default")
      (node (ref "RW5500-2") (pin "4") (pinfunction "1_4") (pintype "passive"))
      (node (ref "U2") (pin "38") (pinfunction "RSVD_38") (pintype "passive"))
    )
    (net (code "109") (name "Net-(SIM900-LED1-PadA)") (class "Default")
      (node (ref "SIM900-LED1") (pin "A") (pinfunction "A_A") (pintype "passive"))
      (node (ref "SIM900-R4") (pin "1") (pinfunction "1_1") (pintype "passive"))
    )
    (net (code "110") (name "Net-(SIM900-LED1-PadC)") (class "Default")
      (node (ref "SIM900-LED1") (pin "C") (pinfunction "C_C") (pintype "passive"))
      (node (ref "SIM900-T1") (pin "C") (pinfunction "C_C") (pintype "passive"))
    )
    (net (code "111") (name "Net-(SIM900-LED2-PadA)") (class "Default")
      (node (ref "SIM900-LED2") (pin "A") (pinfunction "A_A") (pintype "passive"))
      (node (ref "SIM900-R7") (pin "1") (pinfunction "1_1") (pintype "passive"))
    )
    (net (code "112") (name "Net-(SIM900-LED2-PadC)") (class "Default")
      (node (ref "SIM900-LED2") (pin "C") (pinfunction "C_C") (pintype "passive"))
      (node (ref "SIM900-T2") (pin "C") (pinfunction "C_C") (pintype "passive"))
    )
    (net (code "113") (name "Net-(SIM900-R5-Pad1)") (class "Default")
      (node (ref "SIM900-R5") (pin "1") (pinfunction "1_1") (pintype "passive"))
      (node (ref "SIM900-R6") (pin "1") (pinfunction "1_1") (pintype "passive"))
      (node (ref "SIM900-T1") (pin "B") (pinfunction "B_B") (pintype "passive"))
    )
    (net (code "114") (name "Net-(SIM900-R8-Pad1)") (class "Default")
      (node (ref "SIM900-R8") (pin "1") (pinfunction "1_1") (pintype "passive"))
      (node (ref "SIM900-R9") (pin "1") (pinfunction "1_1") (pintype "passive"))
      (node (ref "SIM900-T2") (pin "B") (pinfunction "B_B") (pintype "passive"))
    )
    (net (code "115") (name "Net-(SIM900-R10-Pad2)") (class "Default")
      (node (ref "SIM900-R10") (pin "2") (pinfunction "2_2") (pintype "passive"))
      (node (ref "SIM900-T3") (pin "B") (pinfunction "B_B") (pintype "passive"))
    )
    (net (code "116") (name "Net-(STM_CHIP-PA2)") (class "Default")
      (node (ref "JP_ESP_RX") (pin "2") (pinfunction "2_2") (pintype "passive"))
      (node (ref "STM_CHIP") (pin "16") (pinfunction "PA2_16") (pintype "bidirectional"))
    )
    (net (code "117") (name "Net-(STM_CHIP-PA3)") (class "Default")
      (node (ref "JP_ESP_TX") (pin "2") (pinfunction "2_2") (pintype "passive"))
      (node (ref "STM_CHIP") (pin "17") (pinfunction "PA3_17") (pintype "bidirectional"))
    )
    (net (code "118") (name "Net-(STM_CHIP-PC14-OSC32_IN)") (class "Default")
      (node (ref "STM-C2") (pin "2") (pinfunction "2_2") (pintype "passive"))
      (node (ref "STM-XTAL") (pin "2") (pinfunction "2_2") (pintype "passive"))
      (node (ref "STM_CHIP") (pin "3") (pinfunction "PC14-OSC32_IN_3") (pintype "bidirectional"))
    )
    (net (code "119") (name "Net-(STM_CHIP-PC15-OSC32_OUT)") (class "Default")
      (node (ref "STM-C3") (pin "2") (pinfunction "2_2") (pintype "passive"))
      (node (ref "STM-XTAL") (pin "1") (pinfunction "1_1") (pintype "passive"))
      (node (ref "STM_CHIP") (pin "4") (pinfunction "PC15-OSC32_OUT_4") (pintype "bidirectional"))
    )
    (net (code "120") (name "Net-(U$4B-DCOUPL)") (class "Default")
      (node (ref "CC_DCOUP") (pin "1") (pinfunction "1_1") (pintype "passive"))
      (node (ref "U$4") (pin "27") (pinfunction "DCOUPL_27") (pintype "power_in"))
    )
    (net (code "121") (name "Net-(U$4C-RBIAS)") (class "Default")
      (node (ref "RBIAS") (pin "1") (pinfunction "1_1") (pintype "passive"))
      (node (ref "U$4") (pin "23") (pinfunction "RBIAS_23") (pintype "bidirectional"))
    )
    (net (code "122") (name "Net-(U$4C-VREG-EN)") (class "Default")
      (node (ref "R_VREG") (pin "1") (pinfunction "1_1") (pintype "passive"))
      (node (ref "U$4") (pin "26") (pinfunction "VREG-EN_26") (pintype "input"))
    )
    (net (code "123") (name "Net-(U$4C-XOSC32M-Q1)") (class "Default")
      (node (ref "CC_CX1") (pin "1") (pinfunction "1_1") (pintype "passive"))
      (node (ref "U$4") (pin "13") (pinfunction "XOSC32M-Q1_13") (pintype "input"))
      (node (ref "X1") (pin "1") (pinfunction "1_1") (pintype "bidirectional"))
    )
    (net (code "124") (name "Net-(U$4C-XOSC32M-Q2)") (class "Default")
      (node (ref "CC_CX2") (pin "1") (pinfunction "1_1") (pintype "passive"))
      (node (ref "U$4") (pin "12") (pinfunction "XOSC32M-Q2_12") (pintype "output"))
      (node (ref "X1") (pin "3") (pinfunction "2_3") (pintype "bidirectional"))
    )
    (net (code "125") (name "Net-(U$12-P$2)") (class "Default")
      (node (ref "RT2") (pin "1") (pinfunction "1_1") (pintype "passive"))
      (node (ref "U$12") (pin "PIN$2") (pinfunction "P$2_PIN$2") (pintype "bidirectional"))
    )
    (net (code "126") (name "Net-(U$12-P$3)") (class "Default")
      (node (ref "RT3") (pin "1") (pinfunction "1_1") (pintype "passive"))
      (node (ref "U$12") (pin "PIN$3") (pinfunction "P$3_PIN$3") (pintype "bidirectional"))
    )
    (net (code "127") (name "Net-(U2-1V2O)") (class "Default")
      (node (ref "U2") (pin "22") (pinfunction "1V2O_22") (pintype "passive"))
      (node (ref "W5500-C4") (pin "1") (pinfunction "1_1") (pintype "passive"))
    )
    (net (code "128") (name "Net-(U2-EXRES1)") (class "Default")
      (node (ref "U2") (pin "10") (pinfunction "EXRES1_10") (pintype "passive"))
      (node (ref "W5500-R12") (pin "2") (pinfunction "2_2") (pintype "passive"))
    )
    (net (code "129") (name "Net-(U2-RSVD-Pad23)") (class "Default")
      (node (ref "U2") (pin "23") (pinfunction "RSVD_23") (pintype "passive"))
      (node (ref "W5500-R11") (pin "2") (pinfunction "2_2") (pintype "passive"))
    )
    (net (code "130") (name "Net-(U2-TOCAP)") (class "Default")
      (node (ref "U2") (pin "20") (pinfunction "TOCAP_20") (pintype "passive"))
      (node (ref "W5500-C3") (pin "1") (pinfunction "1_1") (pintype "passive"))
    )
    (net (code "131") (name "Net-(U2-XI{slash}CLKIN)") (class "Default")
      (node (ref "U2") (pin "30") (pinfunction "XI/CLKIN_30") (pintype "passive"))
      (node (ref "W5500-C1") (pin "1") (pinfunction "1_1") (pintype "passive"))
      (node (ref "W5500-R10") (pin "1") (pinfunction "1_1") (pintype "passive"))
      (node (ref "W5500-XTAL") (pin "1") (pinfunction "1_1") (pintype "passive"))
    )
    (net (code "132") (name "Net-(U2-XO)") (class "Default")
      (node (ref "U2") (pin "31") (pinfunction "XO_31") (pintype "passive"))
      (node (ref "W5500-C2") (pin "1") (pinfunction "1_1") (pintype "passive"))
      (node (ref "W5500-R10") (pin "2") (pinfunction "2_2") (pintype "passive"))
      (node (ref "W5500-XTAL") (pin "2") (pinfunction "2_2") (pintype "passive"))
    )
    (net (code "133") (name "Q1") (class "Default")
      (node (ref "IC2") (pin "15") (pinfunction "QA_15") (pintype "tri_state"))
      (node (ref "SR_OUT1") (pin "3") (pinfunction "3_3") (pintype "passive"))
    )
    (net (code "134") (name "Q2") (class "Default")
      (node (ref "IC2") (pin "1") (pinfunction "QB_1") (pintype "tri_state"))
      (node (ref "SR_OUT1") (pin "4") (pinfunction "4_4") (pintype "passive"))
    )
    (net (code "135") (name "Q3") (class "Default")
      (node (ref "IC2") (pin "2") (pinfunction "QC_2") (pintype "tri_state"))
      (node (ref "SR_OUT1") (pin "5") (pinfunction "5_5") (pintype "passive"))
    )
    (net (code "136") (name "Q4") (class "Default")
      (node (ref "IC2") (pin "3") (pinfunction "QD_3") (pintype "tri_state"))
      (node (ref "SR_OUT1") (pin "6") (pinfunction "6_6") (pintype "passive"))
    )
    (net (code "137") (name "Q5") (class "Default")
      (node (ref "IC2") (pin "4") (pinfunction "QE_4") (pintype "tri_state"))
      (node (ref "SR_OUT1") (pin "7") (pinfunction "7_7") (pintype "passive"))
    )
    (net (code "138") (name "Q6") (class "Default")
      (node (ref "IC2") (pin "5") (pinfunction "QF_5") (pintype "tri_state"))
      (node (ref "SR_OUT1") (pin "8") (pinfunction "8_8") (pintype "passive"))
    )
    (net (code "139") (name "Q7") (class "Default")
      (node (ref "IC2") (pin "6") (pinfunction "QG_6") (pintype "tri_state"))
      (node (ref "SR_OUT1") (pin "9") (pinfunction "9_9") (pintype "passive"))
    )
    (net (code "140") (name "Q8") (class "Default")
      (node (ref "IC2") (pin "7") (pinfunction "QH_7") (pintype "tri_state"))
      (node (ref "SR_OUT1") (pin "10") (pinfunction "10_10") (pintype "passive"))
    )
    (net (code "141") (name "Q9") (class "Default")
      (node (ref "IC3") (pin "15") (pinfunction "QA_15") (pintype "tri_state"))
      (node (ref "SR_OUT2") (pin "3") (pinfunction "3_3") (pintype "passive"))
    )
    (net (code "142") (name "Q10") (class "Default")
      (node (ref "IC3") (pin "1") (pinfunction "QB_1") (pintype "tri_state"))
      (node (ref "SR_OUT2") (pin "4") (pinfunction "4_4") (pintype "passive"))
    )
    (net (code "143") (name "Q11") (class "Default")
      (node (ref "IC3") (pin "2") (pinfunction "QC_2") (pintype "tri_state"))
      (node (ref "SR_OUT2") (pin "5") (pinfunction "5_5") (pintype "passive"))
    )
    (net (code "144") (name "Q12") (class "Default")
      (node (ref "IC3") (pin "3") (pinfunction "QD_3") (pintype "tri_state"))
      (node (ref "SR_OUT2") (pin "6") (pinfunction "6_6") (pintype "passive"))
    )
    (net (code "145") (name "Q13") (class "Default")
      (node (ref "IC3") (pin "4") (pinfunction "QE_4") (pintype "tri_state"))
      (node (ref "SR_OUT2") (pin "7") (pinfunction "7_7") (pintype "passive"))
    )
    (net (code "146") (name "Q14") (class "Default")
      (node (ref "IC3") (pin "5") (pinfunction "QF_5") (pintype "tri_state"))
      (node (ref "SR_OUT2") (pin "8") (pinfunction "8_8") (pintype "passive"))
    )
    (net (code "147") (name "Q15") (class "Default")
      (node (ref "IC3") (pin "6") (pinfunction "QG_6") (pintype "tri_state"))
      (node (ref "SR_OUT2") (pin "9") (pinfunction "9_9") (pintype "passive"))
    )
    (net (code "148") (name "Q16") (class "Default")
      (node (ref "IC3") (pin "7") (pinfunction "QH_7") (pintype "tri_state"))
      (node (ref "SR_OUT2") (pin "10") (pinfunction "10_10") (pintype "passive"))
    )
    (net (code "149") (name "QS") (class "Default")
      (node (ref "IC2") (pin "9") (pinfunction "QH*_9") (pintype "tri_state"))
      (node (ref "IC3") (pin "14") (pinfunction "SER_14") (pintype "input"))
    )
    (net (code "150") (name "QS2") (class "Default")
      (node (ref "IC3") (pin "9") (pinfunction "QH*_9") (pintype "tri_state"))
      (node (ref "IC5") (pin "14") (pinfunction "SER_14") (pintype "input"))
    )
    (net (code "151") (name "R") (class "Default")
      (node (ref "RT1") (pin "1") (pinfunction "1_1") (pintype "passive"))
      (node (ref "U$12") (pin "PIN$1") (pinfunction "P$1_PIN$1") (pintype "bidirectional"))
      (node (ref "U$3") (pin "AC$1") (pinfunction "AC_IN$1_AC$1") (pintype "bidirectional"))
    )
    (net (code "152") (name "RXN") (class "Default")
      (node (ref "ETH-C4") (pin "2") (pinfunction "2_2") (pintype "passive"))
      (node (ref "ETH-R7") (pin "1") (pinfunction "1_1") (pintype "passive"))
      (node (ref "U2") (pin "5") (pinfunction "RXN_5") (pintype "passive"))
    )
    (net (code "153") (name "RXP") (class "Default")
      (node (ref "ETH-C2") (pin "2") (pinfunction "2_2") (pintype "passive"))
      (node (ref "ETH-R6") (pin "2") (pinfunction "2_2") (pintype "passive"))
      (node (ref "U2") (pin "6") (pinfunction "RXP_6") (pintype "passive"))
    )
    (net (code "154") (name "SD_CS") (class "Default")
      (node (ref "STM_CHIP") (pin "55") (pinfunction "PB3_55") (pintype "bidirectional"))
      (node (ref "U$13") (pin "SD_CS") (pinfunction "SD_CS_SD_CS") (pintype "bidirectional"))
    )
    (net (code "155") (name "SERIAL_RX") (class "Default")
      (node (ref "STM-USART") (pin "3") (pinfunction "3_3") (pintype "passive"))
      (node (ref "STM_CHIP") (pin "43") (pinfunction "PA10_43") (pintype "bidirectional"))
    )
    (net (code "156") (name "SERIAL_TX") (class "Default")
      (node (ref "STM-USART") (pin "2") (pinfunction "2_2") (pintype "passive"))
      (node (ref "STM_CHIP") (pin "42") (pinfunction "PA9_42") (pintype "bidirectional"))
    )
    (net (code "157") (name "SIM900_PWRKEY") (class "Default")
      (node (ref "IC1") (pin "P$1") (pinfunction "PWRKEY_P$1") (pintype "power_in"))
      (node (ref "SIM900-T3") (pin "C") (pinfunction "C_C") (pintype "passive"))
    )
    (net (code "158") (name "SIM_NETLIGHT") (class "Default")
      (node (ref "IC1") (pin "P$52") (pinfunction "NETLIGHT_P$52") (pintype "bidirectional"))
      (node (ref "SIM900-R8") (pin "2") (pinfunction "2_2") (pintype "passive"))
    )
    (net (code "159") (name "SIM_PWRKEY") (class "Default")
      (node (ref "SIM900-R10") (pin "1") (pinfunction "1_1") (pintype "passive"))
      (node (ref "STM_CHIP") (pin "41") (pinfunction "PA8_41") (pintype "bidirectional"))
    )
    (net (code "160") (name "SIM_RX") (class "Default")
      (node (ref "IC1") (pin "P$10") (pinfunction "RXD_P$10") (pintype "input"))
      (node (ref "STM_CHIP") (pin "51") (pinfunction "PC10_51") (pintype "bidirectional"))
    )
    (net (code "161") (name "SIM_STATUS") (class "Default")
      (node (ref "IC1") (pin "P$66") (pinfunction "STATUS_P$66") (pintype "bidirectional"))
      (node (ref "SIM900-R5") (pin "2") (pinfunction "2_2") (pintype "passive"))
    )
    (net (code "162") (name "SIM_TX") (class "Default")
      (node (ref "IC1") (pin "P$9") (pinfunction "TXD_P$9") (pintype "output"))
      (node (ref "STM_CHIP") (pin "50") (pinfunction "PA15_50") (pintype "bidirectional"))
    )
    (net (code "163") (name "SR_DS") (class "Default")
      (node (ref "IC2") (pin "14") (pinfunction "SER_14") (pintype "input"))
      (node (ref "STM_CHIP") (pin "8") (pinfunction "PC0_8") (pintype "bidirectional"))
    )
    (net (code "164") (name "SR_RST") (class "Default")
      (node (ref "IC2") (pin "10") (pinfunction "SCL_10") (pintype "input"))
      (node (ref "IC3") (pin "10") (pinfunction "SCL_10") (pintype "input"))
      (node (ref "IC5") (pin "10") (pinfunction "SCL_10") (pintype "input"))
      (node (ref "STM_CHIP") (pin "11") (pinfunction "PC3_11") (pintype "bidirectional"))
    )
    (net (code "165") (name "SR_SHCP") (class "Default")
      (node (ref "IC2") (pin "11") (pinfunction "SCK_11") (pintype "input"))
      (node (ref "IC3") (pin "11") (pinfunction "SCK_11") (pintype "input"))
      (node (ref "IC5") (pin "11") (pinfunction "SCK_11") (pintype "input"))
      (node (ref "STM_CHIP") (pin "10") (pinfunction "PC2_10") (pintype "bidirectional"))
    )
    (net (code "166") (name "SR_STCP") (class "Default")
      (node (ref "IC2") (pin "12") (pinfunction "RCK_12") (pintype "input"))
      (node (ref "IC3") (pin "12") (pinfunction "RCK_12") (pintype "input"))
      (node (ref "IC5") (pin "12") (pinfunction "RCK_12") (pintype "input"))
      (node (ref "STM_CHIP") (pin "9") (pinfunction "PC1_9") (pintype "bidirectional"))
    )
    (net (code "167") (name "SWD_NRST") (class "Default")
      (node (ref "S1") (pin "1") (pinfunction "1_1") (pintype "passive"))
      (node (ref "S1") (pin "2") (pinfunction "2_2") (pintype "passive"))
      (node (ref "STM-C8") (pin "1") (pinfunction "1_1") (pintype "passive"))
      (node (ref "STM_CHIP") (pin "7") (pinfunction "NRST_7") (pintype "bidirectional"))
    )
    (net (code "168") (name "SWD_TCK") (class "Default")
      (node (ref "STM-SWD") (pin "2") (pinfunction "2_2") (pintype "passive"))
      (node (ref "STM_CHIP") (pin "49") (pinfunction "PA14_49") (pintype "bidirectional"))
    )
    (net (code "169") (name "SWD_TMS") (class "Default")
      (node (ref "STM-SWD") (pin "4") (pinfunction "4_4") (pintype "passive"))
      (node (ref "STM_CHIP") (pin "46") (pinfunction "PA13_46") (pintype "bidirectional"))
    )
    (net (code "170") (name "TXN") (class "Default")
      (node (ref "ETH-R2") (pin "1") (pinfunction "1_1") (pintype "passive"))
      (node (ref "ETHERNET") (pin "2") (pinfunction "TX-_2") (pintype "bidirectional"))
      (node (ref "U2") (pin "1") (pinfunction "TXN_1") (pintype "passive"))
    )
    (net (code "171") (name "TXP") (class "Default")
      (node (ref "ETH-R1") (pin "1") (pinfunction "1_1") (pintype "passive"))
      (node (ref "ETHERNET") (pin "1") (pinfunction "TX+_1") (pintype "bidirectional"))
      (node (ref "U2") (pin "2") (pinfunction "TXP_2") (pintype "passive"))
    )
    (net (code "172") (name "T_CLK") (class "Default")
      (node (ref "STM_CHIP") (pin "27") (pinfunction "PB1_27") (pintype "bidirectional"))
      (node (ref "U$13") (pin "T_CLK") (pinfunction "T_CLK_T_CLK") (pintype "bidirectional"))
    )
    (net (code "173") (name "T_DIN") (class "Default")
      (node (ref "STM_CHIP") (pin "29") (pinfunction "PB10_29") (pintype "bidirectional"))
      (node (ref "U$13") (pin "T_DIN") (pinfunction "T_DIN_T_DIN") (pintype "bidirectional"))
    )
    (net (code "174") (name "T_DO") (class "Default")
      (node (ref "STM_CHIP") (pin "30") (pinfunction "PB11_30") (pintype "bidirectional"))
      (node (ref "U$13") (pin "T_DO") (pinfunction "T_DO_T_DO") (pintype "bidirectional"))
    )
    (net (code "175") (name "T_IRQ") (class "Default")
      (node (ref "STM_CHIP") (pin "28") (pinfunction "PB2_28") (pintype "bidirectional"))
      (node (ref "U$13") (pin "T_IRQ") (pinfunction "T_IRQ_T_IRQ") (pintype "bidirectional"))
    )
    (net (code "176") (name "USB_DM") (class "Default")
      (node (ref "STM_CHIP") (pin "44") (pinfunction "PA11_44") (pintype "bidirectional"))
      (node (ref "USB_IN") (pin "D-1") (pinfunction "D-_D-1") (pintype "bidirectional"))
    )
    (net (code "177") (name "USB_DP") (class "Default")
      (node (ref "STM_CHIP") (pin "45") (pinfunction "PA12_45") (pintype "bidirectional"))
      (node (ref "USB_IN") (pin "D+1") (pinfunction "D+_D+1") (pintype "bidirectional"))
    )
    (net (code "178") (name "USIM_CLK") (class "Default")
      (node (ref "SIM900-R2") (pin "2") (pinfunction "2_2") (pintype "passive"))
      (node (ref "U$8") (pin "SIM_CLK") (pinfunction "SIM_CLK_SIM_CLK") (pintype "bidirectional"))
    )
    (net (code "179") (name "USIM_DATA") (class "Default")
      (node (ref "SIM900-R3") (pin "2") (pinfunction "2_2") (pintype "passive"))
      (node (ref "U$8") (pin "SIM_IO") (pinfunction "SIM_IO_SIM_IO") (pintype "bidirectional"))
    )
    (net (code "180") (name "USIM_RESET") (class "Default")
      (node (ref "SIM900-R1") (pin "2") (pinfunction "2_2") (pintype "passive"))
      (node (ref "U$8") (pin "SIM_RST") (pinfunction "SIM_RST_SIM_RST") (pintype "bidirectional"))
    )
    (net (code "181") (name "USIM_VCC") (class "Default")
      (node (ref "IC1") (pin "P$30") (pinfunction "SIM_VDD_P$30") (pintype "power_in"))
      (node (ref "SIM900-C4") (pin "1") (pinfunction "1_1") (pintype "passive"))
      (node (ref "SIM900-C5") (pin "1") (pinfunction "1_1") (pintype "passive"))
      (node (ref "SIM_C1") (pin "2") (pinfunction "2_2") (pintype "passive"))
      (node (ref "SIM_C2") (pin "2") (pinfunction "2_2") (pintype "passive"))
      (node (ref "U$8") (pin "SIM_VDD") (pinfunction "SIM_VDD_SIM_VDD") (pintype "bidirectional"))
    )
    (net (code "182") (name "VBAT") (class "Default")
      (node (ref "BAT1") (pin "PWR@1") (pinfunction "+_PWR@1") (pintype "power_in"))
      (node (ref "STM_CHIP") (pin "1") (pinfunction "VLCD_1") (pintype "power_in"))
    )
    (net (code "183") (name "VCC") (class "Default")
      (node (ref "ETH-R1") (pin "2") (pinfunction "2_2") (pintype "passive"))
      (node (ref "ETH-R2") (pin "2") (pinfunction "2_2") (pintype "passive"))
      (node (ref "ETH-R3") (pin "2") (pinfunction "2_2") (pintype "passive"))
      (node (ref "STM-C9") (pin "1") (pinfunction "1_1") (pintype "passive"))
      (node (ref "STM-L1") (pin "2") (pinfunction "2_2") (pintype "passive"))
      (node (ref "STM_CHIP") (pin "13") (pinfunction "VDDA_13") (pintype "power_in"))
      (node (ref "SYS-C4") (pin "1") (pinfunction "1_1") (pintype "passive"))
      (node (ref "SYS-R2") (pin "2") (pinfunction "2_2") (pintype "passive"))
      (node (ref "U2") (pin "11") (pinfunction "AVDD_11") (pintype "passive"))
      (node (ref "U2") (pin "15") (pinfunction "AVDD_15") (pintype "passive"))
      (node (ref "U2") (pin "17") (pinfunction "AVDD_17") (pintype "passive"))
      (node (ref "U2") (pin "21") (pinfunction "AVDD_21") (pintype "passive"))
      (node (ref "U2") (pin "4") (pinfunction "AVDD_4") (pintype "passive"))
      (node (ref "U2") (pin "8") (pinfunction "AVDD_8") (pintype "passive"))
      (node (ref "W5500-C10") (pin "1") (pinfunction "1_1") (pintype "passive"))
      (node (ref "W5500-C11") (pin "1") (pinfunction "1_1") (pintype "passive"))
      (node (ref "W5500-C12") (pin "+") (pinfunction "+_+") (pintype "passive"))
      (node (ref "W5500-C6") (pin "1") (pinfunction "1_1") (pintype "passive"))
      (node (ref "W5500-C7") (pin "1") (pinfunction "1_1") (pintype "passive"))
      (node (ref "W5500-C8") (pin "1") (pinfunction "1_1") (pintype "passive"))
      (node (ref "W5500-C9") (pin "1") (pinfunction "1_1") (pintype "passive"))
    )
    (net (code "184") (name "VDD") (class "Default")
      (node (ref "CC_C14") (pin "1") (pinfunction "1_1") (pintype "passive"))
      (node (ref "CC_C20") (pin "1") (pinfunction "1_1") (pintype "passive"))
      (node (ref "CC_C8") (pin "1") (pinfunction "1_1") (pintype "passive"))
      (node (ref "DHT-R1") (pin "1") (pinfunction "1_1") (pintype "passive"))
      (node (ref "ESP_EXT") (pin "1") (pinfunction "1_1") (pintype "passive"))
      (node (ref "ETHERNET") (pin "12") (pinfunction "LED2_A_12") (pintype "bidirectional"))
      (node (ref "ETHERNET") (pin "9") (pinfunction "LED1_A_9") (pintype "bidirectional"))
      (node (ref "IC2") (pin "16") (pinfunction "VCC_16") (pintype "power_in"))
      (node (ref "IC3") (pin "16") (pinfunction "VCC_16") (pintype "power_in"))
      (node (ref "IC5") (pin "16") (pinfunction "VCC_16") (pintype "power_in"))
      (node (ref "LCD-R1") (pin "2") (pinfunction "2_2") (pintype "passive"))
      (node (ref "PWR-SWT") (pin "1") (pinfunction "1_1") (pintype "passive"))
      (node (ref "RW5500-1") (pin "2") (pinfunction "1_2") (pintype "passive"))
      (node (ref "RW5500-1") (pin "3") (pinfunction "1_3") (pintype "passive"))
      (node (ref "RW5500-1") (pin "4") (pinfunction "1_4") (pintype "passive"))
      (node (ref "RW5500-3") (pin "1") (pinfunction "1_1") (pintype "passive"))
      (node (ref "R_VREG") (pin "2") (pinfunction "2_2") (pintype "passive"))
      (node (ref "SIM900-R4") (pin "2") (pinfunction "2_2") (pintype "passive"))
      (node (ref "SIM900-R7") (pin "2") (pinfunction "2_2") (pintype "passive"))
      (node (ref "STM-C1") (pin "2") (pinfunction "2_2") (pintype "passive"))
      (node (ref "STM-C10") (pin "1") (pinfunction "1_1") (pintype "passive"))
      (node (ref "STM-C11") (pin "1") (pinfunction "1_1") (pintype "passive"))
      (node (ref "STM-C12") (pin "1") (pinfunction "1_1") (pintype "passive"))
      (node (ref "STM-C13") (pin "1") (pinfunction "1_1") (pintype "passive"))
      (node (ref "STM-L1") (pin "1") (pinfunction "1_1") (pintype "passive"))
      (node (ref "STM-SWD") (pin "1") (pinfunction "1_1") (pintype "passive"))
      (node (ref "STM-USART") (pin "1") (pinfunction "1_1") (pintype "passive"))
      (node (ref "STM_CHIP") (pin "19") (pinfunction "VDD_4_19") (pintype "power_in"))
      (node (ref "STM_CHIP") (pin "32") (pinfunction "VDD_1_32") (pintype "power_in"))
      (node (ref "STM_CHIP") (pin "48") (pinfunction "VDD_2_48") (pintype "power_in"))
      (node (ref "STM_CHIP") (pin "64") (pinfunction "VDD_3_64") (pintype "power_in"))
      (node (ref "SYS-C3") (pin "1") (pinfunction "1_1") (pintype "passive"))
      (node (ref "SYS-L2") (pin "2") (pinfunction "2_2") (pintype "passive"))
      (node (ref "SYS-R2") (pin "1") (pinfunction "1_1") (pintype "passive"))
      (node (ref "U$13") (pin "LCD_VCC") (pinfunction "LCD_VCC_LCD_VCC") (pintype "power_in"))
      (node (ref "U$17") (pin "VCC") (pinfunction "VCC_VCC") (pintype "bidirectional"))
      (node (ref "U$4") (pin "11") (pinfunction "AVDD_11") (pintype "power_in"))
      (node (ref "U$4") (pin "14") (pinfunction "AVDD_14") (pintype "power_in"))
      (node (ref "U$4") (pin "16") (pinfunction "AVDD_16") (pintype "power_in"))
      (node (ref "U$4") (pin "20") (pinfunction "AVDD_20") (pintype "power_in"))
      (node (ref "U$4") (pin "22") (pinfunction "AVDD_22") (pintype "power_in"))
      (node (ref "U$4") (pin "24") (pinfunction "AVDD-GUARD_24") (pintype "power_in"))
      (node (ref "U$4") (pin "8") (pinfunction "DVDD_8") (pintype "power_in"))
      (node (ref "U2") (pin "28") (pinfunction "VDD_28") (pintype "passive"))
      (node (ref "W5500-C13") (pin "+") (pinfunction "+_+") (pintype "passive"))
      (node (ref "W5500-C5") (pin "1") (pinfunction "1_1") (pintype "passive"))
      (node (ref "W5500-R13") (pin "2") (pinfunction "2_2") (pintype "passive"))
    )
    (net (code "185") (name "VESP") (class "Default")
      (node (ref "ESP-C1") (pin "1") (pinfunction "1_1") (pintype "passive"))
      (node (ref "ESP-GPIO0") (pin "1") (pinfunction "1_1") (pintype "passive"))
      (node (ref "ESP_EXT") (pin "2") (pinfunction "2_2") (pintype "passive"))
      (node (ref "U$5") (pin "CH_PD") (pinfunction "CH_PD_CH_PD") (pintype "bidirectional"))
      (node (ref "U$5") (pin "GPIO02") (pinfunction "GPIO2_GPIO02") (pintype "bidirectional"))
      (node (ref "U$5") (pin "REST") (pinfunction "REST_REST") (pintype "bidirectional"))
      (node (ref "U$5") (pin "VCC") (pinfunction "VCC_VCC") (pintype "power_in"))
    )
    (net (code "186") (name "unconnected-(IC1-ADC-PadP$25)") (class "Default")
      (node (ref "IC1") (pin "P$25") (pinfunction "ADC_P$25") (pintype "bidirectional"))
    )
    (net (code "187") (name "unconnected-(IC1-CTS-PadP$7)") (class "Default")
      (node (ref "IC1") (pin "P$7") (pinfunction "CTS_P$7") (pintype "output"))
    )
    (net (code "188") (name "unconnected-(IC1-DBG_RXD-PadP$28)") (class "Default")
      (node (ref "IC1") (pin "P$28") (pinfunction "DBG_RXD_P$28") (pintype "input"))
    )
    (net (code "189") (name "unconnected-(IC1-DBG_TXD-PadP$27)") (class "Default")
      (node (ref "IC1") (pin "P$27") (pinfunction "DBG_TXD_P$27") (pintype "output"))
    )
    (net (code "190") (name "unconnected-(IC1-DCD-PadP$5)") (class "Default")
      (node (ref "IC1") (pin "P$5") (pinfunction "DCD_P$5") (pintype "output"))
    )
    (net (code "191") (name "unconnected-(IC1-DISP_CLK-PadP$11)") (class "Default")
      (node (ref "IC1") (pin "P$11") (pinfunction "DISP_CLK_P$11") (pintype "bidirectional"))
    )
    (net (code "192") (name "unconnected-(IC1-DISP_CS-PadP$14)") (class "Default")
      (node (ref "IC1") (pin "P$14") (pinfunction "DISP_CS_P$14") (pintype "bidirectional"))
    )
    (net (code "193") (name "unconnected-(IC1-DISP_DATA-PadP$12)") (class "Default")
      (node (ref "IC1") (pin "P$12") (pinfunction "DISP_DATA_P$12") (pintype "bidirectional"))
    )
    (net (code "194") (name "unconnected-(IC1-DISP_DC-PadP$13)") (class "Default")
      (node (ref "IC1") (pin "P$13") (pinfunction "DISP_DC_P$13") (pintype "bidirectional"))
    )
    (net (code "195") (name "unconnected-(IC1-DTR-PadP$3)") (class "Default")
      (node (ref "IC1") (pin "P$3") (pinfunction "DTR_P$3") (pintype "input"))
    )
    (net (code "196") (name "unconnected-(IC1-GPIO1{slash}KBR4-PadP$40)") (class "Default")
      (node (ref "IC1") (pin "P$40") (pinfunction "GPIO1/KBR4_P$40") (pintype "bidirectional"))
    )
    (net (code "197") (name "unconnected-(IC1-GPIO2{slash}KBR3-PadP$41)") (class "Default")
      (node (ref "IC1") (pin "P$41") (pinfunction "GPIO2/KBR3_P$41") (pintype "bidirectional"))
    )
    (net (code "198") (name "unconnected-(IC1-GPIO3{slash}KBR2-PadP$42)") (class "Default")
      (node (ref "IC1") (pin "P$42") (pinfunction "GPIO3/KBR2_P$42") (pintype "bidirectional"))
    )
    (net (code "199") (name "unconnected-(IC1-GPIO4{slash}KBR1-PadP$43)") (class "Default")
      (node (ref "IC1") (pin "P$43") (pinfunction "GPIO4/KBR1_P$43") (pintype "bidirectional"))
    )
    (net (code "200") (name "unconnected-(IC1-GPIO5{slash}KBR0-PadP$44)") (class "Default")
      (node (ref "IC1") (pin "P$44") (pinfunction "GPIO5/KBR0_P$44") (pintype "bidirectional"))
    )
    (net (code "201") (name "unconnected-(IC1-GPIO6{slash}KBC4-PadP$47)") (class "Default")
      (node (ref "IC1") (pin "P$47") (pinfunction "GPIO6/KBC4_P$47") (pintype "bidirectional"))
    )
    (net (code "202") (name "unconnected-(IC1-GPIO7{slash}KBC3-PadP$48)") (class "Default")
      (node (ref "IC1") (pin "P$48") (pinfunction "GPIO7/KBC3_P$48") (pintype "bidirectional"))
    )
    (net (code "203") (name "unconnected-(IC1-GPIO8{slash}KBC2-PadP$49)") (class "Default")
      (node (ref "IC1") (pin "P$49") (pinfunction "GPIO8/KBC2_P$49") (pintype "bidirectional"))
    )
    (net (code "204") (name "unconnected-(IC1-GPIO9{slash}KBC1-PadP$50)") (class "Default")
      (node (ref "IC1") (pin "P$50") (pinfunction "GPIO9/KBC1_P$50") (pintype "bidirectional"))
    )
    (net (code "205") (name "unconnected-(IC1-GPIO10-PadP$51)") (class "Default")
      (node (ref "IC1") (pin "P$51") (pinfunction "GPIO10_P$51") (pintype "bidirectional"))
    )
    (net (code "206") (name "unconnected-(IC1-LINEIN_L-PadP$24)") (class "Default")
      (node (ref "IC1") (pin "P$24") (pinfunction "LINEIN_L_P$24") (pintype "bidirectional"))
    )
    (net (code "207") (name "unconnected-(IC1-LINEIN_R-PadP$23)") (class "Default")
      (node (ref "IC1") (pin "P$23") (pinfunction "LINEIN_R_P$23") (pintype "bidirectional"))
    )
    (net (code "208") (name "unconnected-(IC1-MIC_N-PadP$20)") (class "Default")
      (node (ref "IC1") (pin "P$20") (pinfunction "MIC_N_P$20") (pintype "bidirectional"))
    )
    (net (code "209") (name "unconnected-(IC1-MIC_P-PadP$19)") (class "Default")
      (node (ref "IC1") (pin "P$19") (pinfunction "MIC_P_P$19") (pintype "bidirectional"))
    )
    (net (code "210") (name "unconnected-(IC1-NC-PadP$2)") (class "Default")
      (node (ref "IC1") (pin "P$2") (pinfunction "NC_P$2") (pintype "no_connect"))
    )
    (net (code "211") (name "unconnected-(IC1-NC-PadP$6)") (class "Default")
      (node (ref "IC1") (pin "P$6") (pinfunction "NC_P$6") (pintype "no_connect"))
    )
    (net (code "212") (name "unconnected-(IC1-NRESET-PadP$16)") (class "Default")
      (node (ref "IC1") (pin "P$16") (pinfunction "NRESET_P$16") (pintype "bidirectional"))
    )
    (net (code "213") (name "unconnected-(IC1-PWM1-PadP$35)") (class "Default")
      (node (ref "IC1") (pin "P$35") (pinfunction "PWM1_P$35") (pintype "bidirectional"))
    )
    (net (code "214") (name "unconnected-(IC1-PWM2-PadP$36)") (class "Default")
      (node (ref "IC1") (pin "P$36") (pinfunction "PWM2_P$36") (pintype "bidirectional"))
    )
    (net (code "215") (name "unconnected-(IC1-RI-PadP$4)") (class "Default")
      (node (ref "IC1") (pin "P$4") (pinfunction "RI_P$4") (pintype "output"))
    )
    (net (code "216") (name "unconnected-(IC1-RTS-PadP$8)") (class "Default")
      (node (ref "IC1") (pin "P$8") (pinfunction "RTS_P$8") (pintype "input"))
    )
    (net (code "217") (name "unconnected-(IC1-SCL-PadP$38)") (class "Default")
      (node (ref "IC1") (pin "P$38") (pinfunction "SCL_P$38") (pintype "bidirectional"))
    )
    (net (code "218") (name "unconnected-(IC1-SDA-PadP$37)") (class "Default")
      (node (ref "IC1") (pin "P$37") (pinfunction "SDA_P$37") (pintype "bidirectional"))
    )
    (net (code "219") (name "unconnected-(IC1-SIM_PRESENCE-PadP$34)") (class "Default")
      (node (ref "IC1") (pin "P$34") (pinfunction "SIM_PRESENCE_P$34") (pintype "bidirectional"))
    )
    (net (code "220") (name "unconnected-(IC1-SPK_N-PadP$22)") (class "Default")
      (node (ref "IC1") (pin "P$22") (pinfunction "SPK_N_P$22") (pintype "bidirectional"))
    )
    (net (code "221") (name "unconnected-(IC1-SPK_P-PadP$21)") (class "Default")
      (node (ref "IC1") (pin "P$21") (pinfunction "SPK_P_P$21") (pintype "bidirectional"))
    )
    (net (code "222") (name "unconnected-(IC1-VDD_EXT-PadP$15)") (class "Default")
      (node (ref "IC1") (pin "P$15") (pinfunction "VDD_EXT_P$15") (pintype "bidirectional"))
    )
    (net (code "223") (name "unconnected-(IC5A-QE-Pad4)") (class "Default")
      (node (ref "IC5") (pin "4") (pinfunction "QE_4") (pintype "tri_state"))
    )
    (net (code "224") (name "unconnected-(IC5A-QF-Pad5)") (class "Default")
      (node (ref "IC5") (pin "5") (pinfunction "QF_5") (pintype "tri_state"))
    )
    (net (code "225") (name "unconnected-(IC5A-QG-Pad6)") (class "Default")
      (node (ref "IC5") (pin "6") (pinfunction "QG_6") (pintype "tri_state"))
    )
    (net (code "226") (name "unconnected-(IC5A-QH*-Pad9)") (class "Default")
      (node (ref "IC5") (pin "9") (pinfunction "QH*_9") (pintype "tri_state"))
    )
    (net (code "227") (name "unconnected-(IC5A-QH-Pad7)") (class "Default")
      (node (ref "IC5") (pin "7") (pinfunction "QH_7") (pintype "tri_state"))
    )
    (net (code "228") (name "unconnected-(STM_CHIP-BOOT0-Pad60)") (class "Default")
      (node (ref "STM_CHIP") (pin "60") (pinfunction "BOOT0_60") (pintype "input"))
    )
    (net (code "229") (name "unconnected-(STM_CHIP-PH0_-OSC_IN-Pad5)") (class "Default")
      (node (ref "STM_CHIP") (pin "5") (pinfunction "PH0_-OSC_IN_5") (pintype "bidirectional"))
    )
    (net (code "230") (name "unconnected-(U$5-GPIO4-PadGPIO04)") (class "Default")
      (node (ref "U$5") (pin "GPIO04") (pinfunction "GPIO4_GPIO04") (pintype "bidirectional"))
    )
    (net (code "231") (name "unconnected-(U$5-GPIO5-PadGPIO05)") (class "Default")
      (node (ref "U$5") (pin "GPIO05") (pinfunction "GPIO5_GPIO05") (pintype "bidirectional"))
    )
    (net (code "232") (name "unconnected-(U$5-PadADC)") (class "Default")
      (node (ref "U$5") (pin "ADC") (pinfunction "ADC_ADC") (pintype "bidirectional"))
    )
    (net (code "233") (name "unconnected-(U$5-PadGPIO12)") (class "Default")
      (node (ref "U$5") (pin "GPIO12") (pinfunction "GPIO12_GPIO12") (pintype "bidirectional"))
    )
    (net (code "234") (name "unconnected-(U$5-PadGPIO13)") (class "Default")
      (node (ref "U$5") (pin "GPIO13") (pinfunction "GPIO13_GPIO13") (pintype "bidirectional"))
    )
    (net (code "235") (name "unconnected-(U$5-PadGPIO14)") (class "Default")
      (node (ref "U$5") (pin "GPIO14") (pinfunction "GPIO14_GPIO14") (pintype "bidirectional"))
    )
    (net (code "236") (name "unconnected-(U$5-PadGPIO16)") (class "Default")
      (node (ref "U$5") (pin "GPIO16") (pinfunction "GPIO16_GPIO16") (pintype "bidirectional"))
    )
    (net (code "237") (name "unconnected-(U$8-PadVPP)") (class "Default")
      (node (ref "U$8") (pin "VPP") (pinfunction "VPP_VPP") (pintype "bidirectional"))
    )
    (net (code "238") (name "unconnected-(U$17-PadNO)") (class "Default")
      (node (ref "U$17") (pin "NO") (pinfunction "NO_NO") (pintype "bidirectional"))
    )
    (net (code "239") (name "unconnected-(U2-DNC-Pad7)") (class "Default")
      (node (ref "U2") (pin "7") (pinfunction "DNC_7") (pintype "passive"))
    )
    (net (code "240") (name "unconnected-(U2-DUPLED-Pad26)") (class "Default")
      (node (ref "U2") (pin "26") (pinfunction "DUPLED_26") (pintype "passive"))
    )
    (net (code "241") (name "unconnected-(U2-INT_N-Pad36)") (class "Default")
      (node (ref "U2") (pin "36") (pinfunction "INT_N_36") (pintype "passive"))
    )
    (net (code "242") (name "unconnected-(U2-NC-Pad12)") (class "Default")
      (node (ref "U2") (pin "12") (pinfunction "NC_12") (pintype "passive"))
    )
    (net (code "243") (name "unconnected-(U2-NC-Pad13)") (class "Default")
      (node (ref "U2") (pin "13") (pinfunction "NC_13") (pintype "passive"))
    )
    (net (code "244") (name "unconnected-(U2-NC-Pad46)") (class "Default")
      (node (ref "U2") (pin "46") (pinfunction "NC_46") (pintype "passive"))
    )
    (net (code "245") (name "unconnected-(U2-NC-Pad47)") (class "Default")
      (node (ref "U2") (pin "47") (pinfunction "NC_47") (pintype "passive"))
    )
    (net (code "246") (name "unconnected-(U2-SPDLED-Pad24)") (class "Default")
      (node (ref "U2") (pin "24") (pinfunction "SPDLED_24") (pintype "passive"))
    )
    (net (code "247") (name "unconnected-(U2-VBG-Pad18)") (class "Default")
      (node (ref "U2") (pin "18") (pinfunction "VBG_18") (pintype "passive"))
    )
    (net (code "248") (name "unconnected-(USB_IN-ID-PadID1)") (class "Default")
      (node (ref "USB_IN") (pin "ID1") (pinfunction "ID_ID1") (pintype "bidirectional"))
    )
  )
)
